# ArtFire_1.net
KiCad netlist of a schematic drawn in Altium Designer
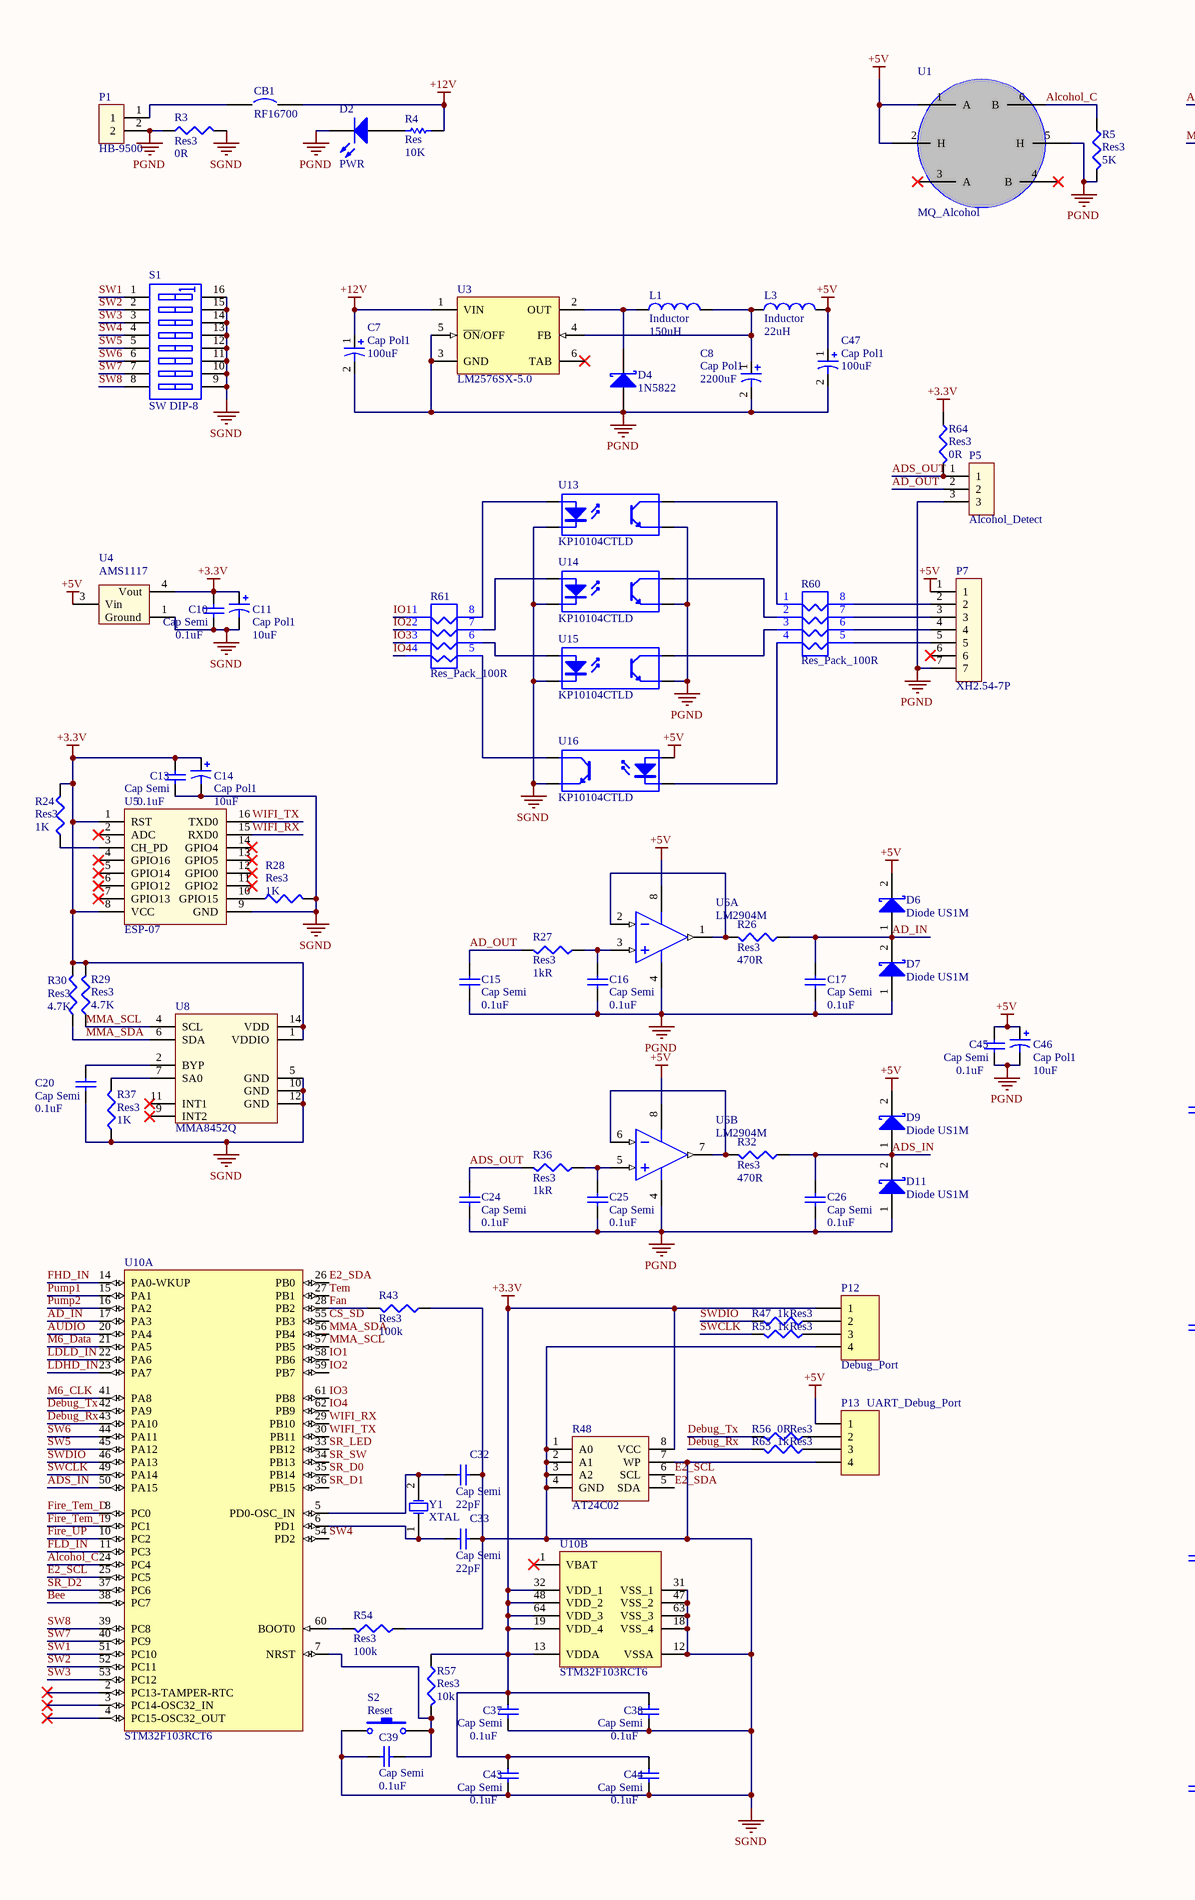
[diagram p0: ArtFire (1).SchDoc, left]
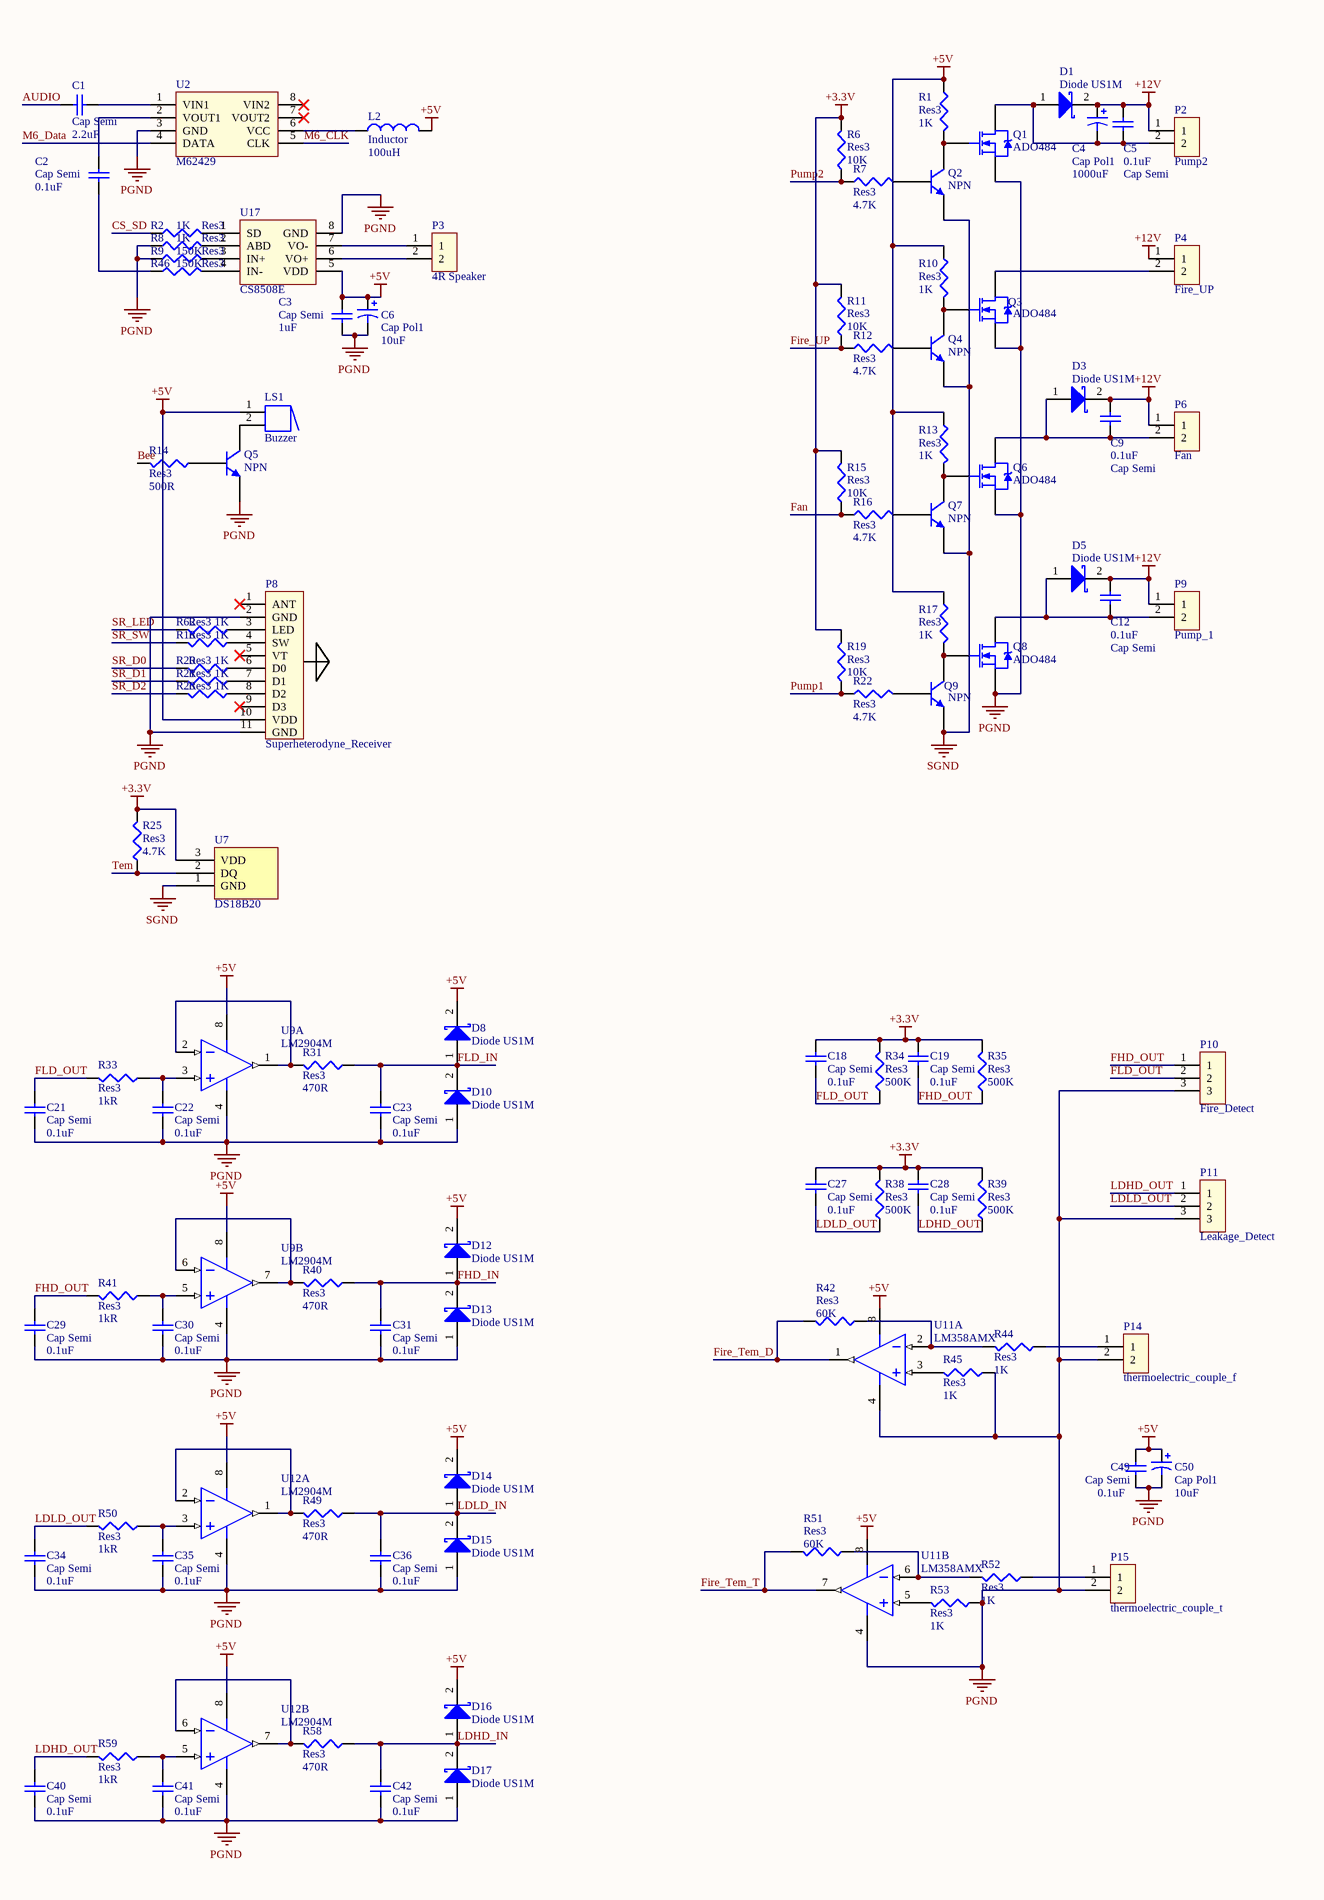
[diagram p1: ArtFire (1).SchDoc, right]

(export (version "E")
  (design (tool "Eeschema 10.0.6"))
  (components
    (comp (ref "C1")
      (value "Cap Semi")
      (footprint "6-0805_N")
      (description "Capacitor (Semiconductor SIM Model)")
      (fields (field (name "ALTIUM_VALUE") "2.2uF") (field (name "PUBLISHER") "Altium Limited"))
      (libsource (lib "Miscellaneous Devices") (part "Cap Semi"))
    )
    (comp (ref "C2")
      (value "Cap Semi")
      (footprint "6-0805_N")
      (description "Capacitor (Semiconductor SIM Model)")
      (fields (field (name "ALTIUM_VALUE") "0.1uF") (field (name "PUBLISHER") "Altium Limited"))
      (libsource (lib "Miscellaneous Devices") (part "Cap Semi"))
    )
    (comp (ref "C3")
      (value "Cap Semi")
      (footprint "6-0805_N")
      (description "Capacitor (Semiconductor SIM Model)")
      (fields (field (name "ALTIUM_VALUE") "1uF") (field (name "PUBLISHER") "Altium Limited"))
      (libsource (lib "Miscellaneous Devices") (part "Cap Semi"))
    )
    (comp (ref "C4")
      (value "Cap Pol1")
      (footprint "CAP_10*10MM")
      (description "Polarized Capacitor (Radial)")
      (fields (field (name "ALTIUM_VALUE") "1000uF") (field (name "PUBLISHER") "Altium Limited"))
      (libsource (lib "Miscellaneous Devices") (part "Cap Pol1"))
    )
    (comp (ref "C5")
      (value "Cap Semi")
      (footprint "6-0805_N")
      (description "Capacitor (Semiconductor SIM Model)")
      (fields (field (name "ALTIUM_VALUE") "0.1uF") (field (name "PUBLISHER") "Altium Limited"))
      (libsource (lib "Miscellaneous Devices") (part "Cap Semi"))
    )
    (comp (ref "C6")
      (value "Cap Pol1")
      (footprint "Cap_5*4mm")
      (description "Polarized Capacitor (Radial)")
      (fields (field (name "ALTIUM_VALUE") "10uF") (field (name "PUBLISHER") "Altium Limited"))
      (libsource (lib "Miscellaneous Devices") (part "Cap Pol1"))
    )
    (comp (ref "C7")
      (value "Cap Pol1")
      (footprint "CAP_6.3*5.4MM")
      (description "Polarized Capacitor (Radial)")
      (fields (field (name "ALTIUM_VALUE") "100uF") (field (name "PUBLISHER") "Altium Limited"))
      (libsource (lib "") (part "Cap Pol1_1"))
    )
    (comp (ref "C8")
      (value "Cap Pol1")
      (footprint "CAP10_17")
      (description "Polarized Capacitor (Radial)")
      (fields (field (name "ALTIUM_VALUE") "2200uF") (field (name "PUBLISHER") "Altium Limited"))
      (libsource (lib "") (part "Cap Pol1_1"))
    )
    (comp (ref "C9")
      (value "Cap Semi")
      (footprint "6-0805_N")
      (description "Capacitor (Semiconductor SIM Model)")
      (fields (field (name "ALTIUM_VALUE") "0.1uF") (field (name "PUBLISHER") "Altium Limited"))
      (libsource (lib "Miscellaneous Devices") (part "Cap Semi"))
    )
    (comp (ref "C10")
      (value "Cap Semi")
      (footprint "6-0805_N")
      (description "Capacitor (Semiconductor SIM Model)")
      (fields (field (name "ALTIUM_VALUE") "0.1uF") (field (name "PUBLISHER") "Altium Limited"))
      (libsource (lib "Miscellaneous Devices") (part "Cap Semi"))
    )
    (comp (ref "C11")
      (value "Cap Pol1")
      (footprint "Cap_5*4mm")
      (description "Polarized Capacitor (Radial)")
      (fields (field (name "ALTIUM_VALUE") "10uF") (field (name "PUBLISHER") "Altium Limited"))
      (libsource (lib "Miscellaneous Devices") (part "Cap Pol1"))
    )
    (comp (ref "C12")
      (value "Cap Semi")
      (footprint "6-0805_N")
      (description "Capacitor (Semiconductor SIM Model)")
      (fields (field (name "ALTIUM_VALUE") "0.1uF") (field (name "PUBLISHER") "Altium Limited"))
      (libsource (lib "Miscellaneous Devices") (part "Cap Semi"))
    )
    (comp (ref "C13")
      (value "Cap Semi")
      (footprint "6-0805_N")
      (description "Capacitor (Semiconductor SIM Model)")
      (fields (field (name "ALTIUM_VALUE") "0.1uF") (field (name "PUBLISHER") "Altium Limited"))
      (libsource (lib "Miscellaneous Devices") (part "Cap Semi"))
    )
    (comp (ref "C14")
      (value "Cap Pol1")
      (footprint "Cap_5*4mm")
      (description "Polarized Capacitor (Radial)")
      (fields (field (name "ALTIUM_VALUE") "10uF") (field (name "PUBLISHER") "Altium Limited"))
      (libsource (lib "Miscellaneous Devices") (part "Cap Pol1"))
    )
    (comp (ref "C15")
      (value "Cap Semi")
      (footprint "6-0805_N")
      (description "Capacitor (Semiconductor SIM Model)")
      (fields (field (name "ALTIUM_VALUE") "0.1uF") (field (name "PUBLISHER") "Altium Limited"))
      (libsource (lib "Miscellaneous Devices") (part "Cap Semi"))
    )
    (comp (ref "C16")
      (value "Cap Semi")
      (footprint "6-0805_N")
      (description "Capacitor (Semiconductor SIM Model)")
      (fields (field (name "ALTIUM_VALUE") "0.1uF") (field (name "PUBLISHER") "Altium Limited"))
      (libsource (lib "Miscellaneous Devices") (part "Cap Semi"))
    )
    (comp (ref "C17")
      (value "Cap Semi")
      (footprint "6-0805_N")
      (description "Capacitor (Semiconductor SIM Model)")
      (fields (field (name "ALTIUM_VALUE") "0.1uF") (field (name "PUBLISHER") "Altium Limited"))
      (libsource (lib "Miscellaneous Devices") (part "Cap Semi"))
    )
    (comp (ref "C18")
      (value "Cap Semi")
      (footprint "6-0805_N")
      (description "Capacitor (Semiconductor SIM Model)")
      (fields (field (name "ALTIUM_VALUE") "0.1uF") (field (name "PUBLISHER") "Altium Limited"))
      (libsource (lib "Miscellaneous Devices") (part "Cap Semi"))
    )
    (comp (ref "C19")
      (value "Cap Semi")
      (footprint "6-0805_N")
      (description "Capacitor (Semiconductor SIM Model)")
      (fields (field (name "ALTIUM_VALUE") "0.1uF") (field (name "PUBLISHER") "Altium Limited"))
      (libsource (lib "Miscellaneous Devices") (part "Cap Semi"))
    )
    (comp (ref "C20")
      (value "Cap Semi")
      (footprint "6-0805_N")
      (description "Capacitor (Semiconductor SIM Model)")
      (fields (field (name "ALTIUM_VALUE") "0.1uF") (field (name "PUBLISHER") "Altium Limited"))
      (libsource (lib "Miscellaneous Devices") (part "Cap Semi"))
    )
    (comp (ref "C21")
      (value "Cap Semi")
      (footprint "6-0805_N")
      (description "Capacitor (Semiconductor SIM Model)")
      (fields (field (name "ALTIUM_VALUE") "0.1uF") (field (name "PUBLISHER") "Altium Limited"))
      (libsource (lib "Miscellaneous Devices") (part "Cap Semi"))
    )
    (comp (ref "C22")
      (value "Cap Semi")
      (footprint "6-0805_N")
      (description "Capacitor (Semiconductor SIM Model)")
      (fields (field (name "ALTIUM_VALUE") "0.1uF") (field (name "PUBLISHER") "Altium Limited"))
      (libsource (lib "Miscellaneous Devices") (part "Cap Semi"))
    )
    (comp (ref "C23")
      (value "Cap Semi")
      (footprint "6-0805_N")
      (description "Capacitor (Semiconductor SIM Model)")
      (fields (field (name "ALTIUM_VALUE") "0.1uF") (field (name "PUBLISHER") "Altium Limited"))
      (libsource (lib "Miscellaneous Devices") (part "Cap Semi"))
    )
    (comp (ref "C24")
      (value "Cap Semi")
      (footprint "6-0805_N")
      (description "Capacitor (Semiconductor SIM Model)")
      (fields (field (name "ALTIUM_VALUE") "0.1uF") (field (name "PUBLISHER") "Altium Limited"))
      (libsource (lib "Miscellaneous Devices") (part "Cap Semi"))
    )
    (comp (ref "C25")
      (value "Cap Semi")
      (footprint "6-0805_N")
      (description "Capacitor (Semiconductor SIM Model)")
      (fields (field (name "ALTIUM_VALUE") "0.1uF") (field (name "PUBLISHER") "Altium Limited"))
      (libsource (lib "Miscellaneous Devices") (part "Cap Semi"))
    )
    (comp (ref "C26")
      (value "Cap Semi")
      (footprint "6-0805_N")
      (description "Capacitor (Semiconductor SIM Model)")
      (fields (field (name "ALTIUM_VALUE") "0.1uF") (field (name "PUBLISHER") "Altium Limited"))
      (libsource (lib "Miscellaneous Devices") (part "Cap Semi"))
    )
    (comp (ref "C27")
      (value "Cap Semi")
      (footprint "6-0805_N")
      (description "Capacitor (Semiconductor SIM Model)")
      (fields (field (name "ALTIUM_VALUE") "0.1uF") (field (name "PUBLISHER") "Altium Limited"))
      (libsource (lib "Miscellaneous Devices") (part "Cap Semi"))
    )
    (comp (ref "C28")
      (value "Cap Semi")
      (footprint "6-0805_N")
      (description "Capacitor (Semiconductor SIM Model)")
      (fields (field (name "ALTIUM_VALUE") "0.1uF") (field (name "PUBLISHER") "Altium Limited"))
      (libsource (lib "Miscellaneous Devices") (part "Cap Semi"))
    )
    (comp (ref "C29")
      (value "Cap Semi")
      (footprint "6-0805_N")
      (description "Capacitor (Semiconductor SIM Model)")
      (fields (field (name "ALTIUM_VALUE") "0.1uF") (field (name "PUBLISHER") "Altium Limited"))
      (libsource (lib "Miscellaneous Devices") (part "Cap Semi"))
    )
    (comp (ref "C30")
      (value "Cap Semi")
      (footprint "6-0805_N")
      (description "Capacitor (Semiconductor SIM Model)")
      (fields (field (name "ALTIUM_VALUE") "0.1uF") (field (name "PUBLISHER") "Altium Limited"))
      (libsource (lib "Miscellaneous Devices") (part "Cap Semi"))
    )
    (comp (ref "C31")
      (value "Cap Semi")
      (footprint "6-0805_N")
      (description "Capacitor (Semiconductor SIM Model)")
      (fields (field (name "ALTIUM_VALUE") "0.1uF") (field (name "PUBLISHER") "Altium Limited"))
      (libsource (lib "Miscellaneous Devices") (part "Cap Semi"))
    )
    (comp (ref "C32")
      (value "Cap Semi")
      (footprint "6-0805_N")
      (description "Capacitor (Semiconductor SIM Model)")
      (fields (field (name "ALTIUM_VALUE") "22pF") (field (name "PUBLISHER") "Altium Limited"))
      (libsource (lib "Miscellaneous Devices") (part "Cap Semi"))
    )
    (comp (ref "C33")
      (value "Cap Semi")
      (footprint "6-0805_N")
      (description "Capacitor (Semiconductor SIM Model)")
      (fields (field (name "ALTIUM_VALUE") "22pF") (field (name "PUBLISHER") "Altium Limited"))
      (libsource (lib "Miscellaneous Devices") (part "Cap Semi"))
    )
    (comp (ref "C34")
      (value "Cap Semi")
      (footprint "6-0805_N")
      (description "Capacitor (Semiconductor SIM Model)")
      (fields (field (name "ALTIUM_VALUE") "0.1uF") (field (name "PUBLISHER") "Altium Limited"))
      (libsource (lib "Miscellaneous Devices") (part "Cap Semi"))
    )
    (comp (ref "C35")
      (value "Cap Semi")
      (footprint "6-0805_N")
      (description "Capacitor (Semiconductor SIM Model)")
      (fields (field (name "ALTIUM_VALUE") "0.1uF") (field (name "PUBLISHER") "Altium Limited"))
      (libsource (lib "Miscellaneous Devices") (part "Cap Semi"))
    )
    (comp (ref "C36")
      (value "Cap Semi")
      (footprint "6-0805_N")
      (description "Capacitor (Semiconductor SIM Model)")
      (fields (field (name "ALTIUM_VALUE") "0.1uF") (field (name "PUBLISHER") "Altium Limited"))
      (libsource (lib "Miscellaneous Devices") (part "Cap Semi"))
    )
    (comp (ref "C37")
      (value "Cap Semi")
      (footprint "6-0805_N")
      (description "Capacitor (Semiconductor SIM Model)")
      (fields (field (name "ALTIUM_VALUE") "0.1uF") (field (name "PUBLISHER") "Altium Limited"))
      (libsource (lib "Miscellaneous Devices") (part "Cap Semi"))
    )
    (comp (ref "C38")
      (value "Cap Semi")
      (footprint "6-0805_N")
      (description "Capacitor (Semiconductor SIM Model)")
      (fields (field (name "ALTIUM_VALUE") "0.1uF") (field (name "PUBLISHER") "Altium Limited"))
      (libsource (lib "Miscellaneous Devices") (part "Cap Semi"))
    )
    (comp (ref "C39")
      (value "Cap Semi")
      (footprint "6-0805_N")
      (description "Capacitor (Semiconductor SIM Model)")
      (fields (field (name "ALTIUM_VALUE") "0.1uF") (field (name "PUBLISHER") "Altium Limited"))
      (libsource (lib "Miscellaneous Devices") (part "Cap Semi"))
    )
    (comp (ref "C40")
      (value "Cap Semi")
      (footprint "6-0805_N")
      (description "Capacitor (Semiconductor SIM Model)")
      (fields (field (name "ALTIUM_VALUE") "0.1uF") (field (name "PUBLISHER") "Altium Limited"))
      (libsource (lib "Miscellaneous Devices") (part "Cap Semi"))
    )
    (comp (ref "C41")
      (value "Cap Semi")
      (footprint "6-0805_N")
      (description "Capacitor (Semiconductor SIM Model)")
      (fields (field (name "ALTIUM_VALUE") "0.1uF") (field (name "PUBLISHER") "Altium Limited"))
      (libsource (lib "Miscellaneous Devices") (part "Cap Semi"))
    )
    (comp (ref "C42")
      (value "Cap Semi")
      (footprint "6-0805_N")
      (description "Capacitor (Semiconductor SIM Model)")
      (fields (field (name "ALTIUM_VALUE") "0.1uF") (field (name "PUBLISHER") "Altium Limited"))
      (libsource (lib "Miscellaneous Devices") (part "Cap Semi"))
    )
    (comp (ref "C43")
      (value "Cap Semi")
      (footprint "6-0805_N")
      (description "Capacitor (Semiconductor SIM Model)")
      (fields (field (name "ALTIUM_VALUE") "0.1uF") (field (name "PUBLISHER") "Altium Limited"))
      (libsource (lib "Miscellaneous Devices") (part "Cap Semi"))
    )
    (comp (ref "C44")
      (value "Cap Semi")
      (footprint "6-0805_N")
      (description "Capacitor (Semiconductor SIM Model)")
      (fields (field (name "ALTIUM_VALUE") "0.1uF") (field (name "PUBLISHER") "Altium Limited"))
      (libsource (lib "Miscellaneous Devices") (part "Cap Semi"))
    )
    (comp (ref "C45")
      (value "Cap Semi")
      (footprint "6-0805_N")
      (description "Capacitor (Semiconductor SIM Model)")
      (fields (field (name "ALTIUM_VALUE") "0.1uF") (field (name "PUBLISHER") "Altium Limited"))
      (libsource (lib "Miscellaneous Devices") (part "Cap Semi"))
    )
    (comp (ref "C46")
      (value "Cap Pol1")
      (footprint "Cap_5*4mm")
      (description "Polarized Capacitor (Radial)")
      (fields (field (name "ALTIUM_VALUE") "10uF") (field (name "PUBLISHER") "Altium Limited"))
      (libsource (lib "Miscellaneous Devices") (part "Cap Pol1"))
    )
    (comp (ref "C47")
      (value "Cap Pol1")
      (footprint "CAP_6.3*5.4MM")
      (description "Polarized Capacitor (Radial)")
      (fields (field (name "ALTIUM_VALUE") "100uF") (field (name "PUBLISHER") "Altium Limited"))
      (libsource (lib "") (part "Cap Pol1_1"))
    )
    (comp (ref "C49")
      (value "Cap Semi")
      (footprint "6-0805_N")
      (description "Capacitor (Semiconductor SIM Model)")
      (fields (field (name "ALTIUM_VALUE") "0.1uF") (field (name "PUBLISHER") "Altium Limited"))
      (libsource (lib "Miscellaneous Devices") (part "Cap Semi"))
    )
    (comp (ref "C50")
      (value "Cap Pol1")
      (footprint "Cap_5*4mm")
      (description "Polarized Capacitor (Radial)")
      (fields (field (name "ALTIUM_VALUE") "10uF") (field (name "PUBLISHER") "Altium Limited"))
      (libsource (lib "Miscellaneous Devices") (part "Cap Pol1"))
    )
    (comp (ref "CB1")
      (value "RF16700")
      (footprint "SPST-2")
      (description "Circuit Breaker")
      (fields (field (name "PUBLISHER") "Altium Limited"))
      (libsource (lib "Miscellaneous Devices") (part "Circuit Breaker"))
    )
    (comp (ref "D1")
      (value "Diode US1M")
      (footprint "US1M")
      (description "Silicon RF Schottky Diode for Mixer Applications in the VHF/UHF Range")
      (fields (field (name "PUBLISHER") "Altium Limited"))
      (libsource (lib "Miscellaneous Devices") (part "Diode BAT17"))
    )
    (comp (ref "D2")
      (value "PWR")
      (footprint "6-0805_N")
      (description "Typical INFRARED GaAs LED")
      (fields (field (name "PUBLISHER") "Altium Limited"))
      (libsource (lib "Miscellaneous Devices") (part "LED0"))
    )
    (comp (ref "D3")
      (value "Diode US1M")
      (footprint "US1M")
      (description "Silicon RF Schottky Diode for Mixer Applications in the VHF/UHF Range")
      (fields (field (name "PUBLISHER") "Altium Limited"))
      (libsource (lib "Miscellaneous Devices") (part "Diode BAT17"))
    )
    (comp (ref "D4")
      (value "1N5822")
      (footprint "US1M")
      (description "Silicon RF Schottky Diode for Mixer Applications in the VHF/UHF Range")
      (fields (field (name "PUBLISHER") "Altium Limited"))
      (libsource (lib "") (part "Diode BAT17_1"))
    )
    (comp (ref "D5")
      (value "Diode US1M")
      (footprint "US1M")
      (description "Silicon RF Schottky Diode for Mixer Applications in the VHF/UHF Range")
      (fields (field (name "PUBLISHER") "Altium Limited"))
      (libsource (lib "Miscellaneous Devices") (part "Diode BAT17"))
    )
    (comp (ref "D6")
      (value "Diode US1M")
      (footprint "US1M")
      (description "Silicon RF Schottky Diode for Mixer Applications in the VHF/UHF Range")
      (fields (field (name "PUBLISHER") "Altium Limited"))
      (libsource (lib "Miscellaneous Devices") (part "Diode BAT17"))
    )
    (comp (ref "D7")
      (value "Diode US1M")
      (footprint "US1M")
      (description "Silicon RF Schottky Diode for Mixer Applications in the VHF/UHF Range")
      (fields (field (name "PUBLISHER") "Altium Limited"))
      (libsource (lib "Miscellaneous Devices") (part "Diode BAT17"))
    )
    (comp (ref "D8")
      (value "Diode US1M")
      (footprint "US1M")
      (description "Silicon RF Schottky Diode for Mixer Applications in the VHF/UHF Range")
      (fields (field (name "PUBLISHER") "Altium Limited"))
      (libsource (lib "Miscellaneous Devices") (part "Diode BAT17"))
    )
    (comp (ref "D9")
      (value "Diode US1M")
      (footprint "US1M")
      (description "Silicon RF Schottky Diode for Mixer Applications in the VHF/UHF Range")
      (fields (field (name "PUBLISHER") "Altium Limited"))
      (libsource (lib "Miscellaneous Devices") (part "Diode BAT17"))
    )
    (comp (ref "D10")
      (value "Diode US1M")
      (footprint "US1M")
      (description "Silicon RF Schottky Diode for Mixer Applications in the VHF/UHF Range")
      (fields (field (name "PUBLISHER") "Altium Limited"))
      (libsource (lib "Miscellaneous Devices") (part "Diode BAT17"))
    )
    (comp (ref "D11")
      (value "Diode US1M")
      (footprint "US1M")
      (description "Silicon RF Schottky Diode for Mixer Applications in the VHF/UHF Range")
      (fields (field (name "PUBLISHER") "Altium Limited"))
      (libsource (lib "Miscellaneous Devices") (part "Diode BAT17"))
    )
    (comp (ref "D12")
      (value "Diode US1M")
      (footprint "US1M")
      (description "Silicon RF Schottky Diode for Mixer Applications in the VHF/UHF Range")
      (fields (field (name "PUBLISHER") "Altium Limited"))
      (libsource (lib "Miscellaneous Devices") (part "Diode BAT17"))
    )
    (comp (ref "D13")
      (value "Diode US1M")
      (footprint "US1M")
      (description "Silicon RF Schottky Diode for Mixer Applications in the VHF/UHF Range")
      (fields (field (name "PUBLISHER") "Altium Limited"))
      (libsource (lib "Miscellaneous Devices") (part "Diode BAT17"))
    )
    (comp (ref "D14")
      (value "Diode US1M")
      (footprint "US1M")
      (description "Silicon RF Schottky Diode for Mixer Applications in the VHF/UHF Range")
      (fields (field (name "PUBLISHER") "Altium Limited"))
      (libsource (lib "Miscellaneous Devices") (part "Diode BAT17"))
    )
    (comp (ref "D15")
      (value "Diode US1M")
      (footprint "US1M")
      (description "Silicon RF Schottky Diode for Mixer Applications in the VHF/UHF Range")
      (fields (field (name "PUBLISHER") "Altium Limited"))
      (libsource (lib "Miscellaneous Devices") (part "Diode BAT17"))
    )
    (comp (ref "D16")
      (value "Diode US1M")
      (footprint "US1M")
      (description "Silicon RF Schottky Diode for Mixer Applications in the VHF/UHF Range")
      (fields (field (name "PUBLISHER") "Altium Limited"))
      (libsource (lib "Miscellaneous Devices") (part "Diode BAT17"))
    )
    (comp (ref "D17")
      (value "Diode US1M")
      (footprint "US1M")
      (description "Silicon RF Schottky Diode for Mixer Applications in the VHF/UHF Range")
      (fields (field (name "PUBLISHER") "Altium Limited"))
      (libsource (lib "Miscellaneous Devices") (part "Diode BAT17"))
    )
    (comp (ref "L1")
      (value "Inductor")
      (footprint "CDRH127")
      (fields (field (name "ALTIUM_VALUE") "150uH") (field (name "PUBLISHER") "Altium Limited"))
      (libsource (lib "Miscellaneous Devices") (part "Inductor"))
    )
    (comp (ref "L2")
      (value "Inductor")
      (footprint "6-0805_L")
      (fields (field (name "ALTIUM_VALUE") "100uH") (field (name "PUBLISHER") "Altium Limited"))
      (libsource (lib "Miscellaneous Devices") (part "Inductor"))
    )
    (comp (ref "L3")
      (value "Inductor")
      (footprint "IND_0630")
      (fields (field (name "ALTIUM_VALUE") "22uH") (field (name "PUBLISHER") "Altium Limited"))
      (libsource (lib "Miscellaneous Devices") (part "Inductor"))
    )
    (comp (ref "LS1")
      (value "Buzzer")
      (footprint "BUZZER")
      (description "Magnetic Transducer Buzzer")
      (fields (field (name "PUBLISHER") "Altium Limited"))
      (libsource (lib "Miscellaneous Devices") (part "Buzzer"))
    )
    (comp (ref "P1")
      (value "HB-9500")
      (footprint "HB-9500")
      (description "High current connector")
      (libsource (lib "Simon'Library") (part "HB-9500"))
    )
    (comp (ref "P2") (value "Pump2") (footprint "CH3.96_2P") (libsource (lib "CH3.96") (part "CH3.96_2P")))
    (comp (ref "P3")
      (value "4R Speaker")
      (footprint "XH2.54-2P")
      (libsource (lib "XH2.54") (part "XH2.54-2P"))
    )
    (comp (ref "P4") (value "Fire_UP") (footprint "KF7.62-2P") (libsource (lib "KF3.96") (part "KF3.96")))
    (comp (ref "P5")
      (value "Alcohol_Detect")
      (footprint "XH2.54-3P")
      (libsource (lib "XH2.54") (part "XH2.54-3P"))
    )
    (comp (ref "P6") (value "Fan") (footprint "XH2.54-2P") (libsource (lib "XH2.54") (part "XH2.54-2P")))
    (comp (ref "P7")
      (value "XH2.54-7P")
      (footprint "XH2.54-7P")
      (libsource (lib "XH2.54") (part "XH2.54-7P"))
    )
    (comp (ref "P8")
      (value "Superheterodyne_Receiver")
      (footprint "Sperheterodyne_Receiver")
      (libsource (lib "Simon'Library") (part "Superheterodyne_Receiver"))
    )
    (comp (ref "P9") (value "Pump_1") (footprint "CH3.96_2P") (libsource (lib "CH3.96") (part "CH3.96_2P")))
    (comp (ref "P10")
      (value "Fire_Detect")
      (footprint "CH3.96_3P")
      (libsource (lib "CH3.96") (part "CH3.96_3P"))
    )
    (comp (ref "P11")
      (value "Leakage_Detect")
      (footprint "XH2.54-3P")
      (libsource (lib "XH2.54") (part "XH2.54-3P"))
    )
    (comp (ref "P12")
      (value "Debug_Port")
      (footprint "HDR1X4")
      (description "Header, 4-Pin")
      (fields (field (name "PUBLISHER") "Altium Limited"))
      (libsource (lib "Miscellaneous Connectors") (part "Header 4"))
    )
    (comp (ref "P13")
      (value "UART_Debug_Port")
      (footprint "HDR1X4")
      (description "Header, 4-Pin")
      (fields (field (name "PUBLISHER") "Altium Limited"))
      (libsource (lib "Miscellaneous Connectors") (part "Header 4"))
    )
    (comp (ref "P14")
      (value "thermoelectric_couple_f")
      (footprint "KF7.62-2P")
      (libsource (lib "KF3.96") (part "KF3.96"))
    )
    (comp (ref "P15")
      (value "thermoelectric_couple_t")
      (footprint "KF7.62-2P")
      (libsource (lib "KF3.96") (part "KF3.96"))
    )
    (comp (ref "Q1")
      (value "ADO484")
      (footprint "DPAK_AOD484")
      (description "N-Channel Power MOSFET")
      (fields (field (name "PUBLISHER") "Altium Limited"))
      (libsource (lib "Miscellaneous Devices") (part "NMOS-2"))
    )
    (comp (ref "Q2")
      (value "NPN")
      (footprint "SOT-23_N")
      (description "NPN Bipolar Transistor")
      (fields (field (name "PUBLISHER") "Altium Limited"))
      (libsource (lib "Miscellaneous Devices") (part "NPN"))
    )
    (comp (ref "Q3")
      (value "ADO484")
      (footprint "DPAK_AOD484")
      (description "N-Channel Power MOSFET")
      (fields (field (name "PUBLISHER") "Altium Limited"))
      (libsource (lib "Miscellaneous Devices") (part "NMOS-2"))
    )
    (comp (ref "Q4")
      (value "NPN")
      (footprint "SOT-23_N")
      (description "NPN Bipolar Transistor")
      (fields (field (name "PUBLISHER") "Altium Limited"))
      (libsource (lib "Miscellaneous Devices") (part "NPN"))
    )
    (comp (ref "Q5")
      (value "NPN")
      (footprint "SOT-23_N")
      (description "NPN Bipolar Transistor")
      (fields (field (name "PUBLISHER") "Altium Limited"))
      (libsource (lib "Miscellaneous Devices") (part "NPN"))
    )
    (comp (ref "Q6")
      (value "ADO484")
      (footprint "DPAK_AOD484")
      (description "N-Channel Power MOSFET")
      (fields (field (name "PUBLISHER") "Altium Limited"))
      (libsource (lib "Miscellaneous Devices") (part "NMOS-2"))
    )
    (comp (ref "Q7")
      (value "NPN")
      (footprint "SOT-23_N")
      (description "NPN Bipolar Transistor")
      (fields (field (name "PUBLISHER") "Altium Limited"))
      (libsource (lib "Miscellaneous Devices") (part "NPN"))
    )
    (comp (ref "Q8")
      (value "ADO484")
      (footprint "DPAK_AOD484")
      (description "N-Channel Power MOSFET")
      (fields (field (name "PUBLISHER") "Altium Limited"))
      (libsource (lib "Miscellaneous Devices") (part "NMOS-2"))
    )
    (comp (ref "Q9")
      (value "NPN")
      (footprint "SOT-23_N")
      (description "NPN Bipolar Transistor")
      (fields (field (name "PUBLISHER") "Altium Limited"))
      (libsource (lib "Miscellaneous Devices") (part "NPN"))
    )
    (comp (ref "R1")
      (value "Res3")
      (footprint "6-0805_N")
      (description "Resistor")
      (fields (field (name "ALTIUM_VALUE") "1K") (field (name "PUBLISHER") "Altium Limited"))
      (libsource (lib "Miscellaneous Devices") (part "Res3"))
    )
    (comp (ref "R2")
      (value "Res3")
      (footprint "6-0805_N")
      (description "Resistor")
      (fields (field (name "ALTIUM_VALUE") "1K") (field (name "PUBLISHER") "Altium Limited"))
      (libsource (lib "Miscellaneous Devices") (part "Res3"))
    )
    (comp (ref "R3")
      (value "Res3")
      (footprint "6-0805_N")
      (description "Resistor")
      (fields (field (name "ALTIUM_VALUE") "0R") (field (name "PUBLISHER") "Altium Limited"))
      (libsource (lib "Miscellaneous Devices") (part "Res3"))
    )
    (comp (ref "R4")
      (value "Res")
      (footprint "6-0805_N")
      (description "Resistor")
      (fields (field (name "ALTIUM_VALUE") "10K") (field (name "PUBLISHER") "Altium Limited"))
      (libsource (lib "Miscellaneous Devices") (part "Res1"))
    )
    (comp (ref "R5")
      (value "Res3")
      (footprint "6-0805_N")
      (description "Resistor")
      (fields (field (name "ALTIUM_VALUE") "5K") (field (name "PUBLISHER") "Altium Limited"))
      (libsource (lib "Miscellaneous Devices") (part "Res3"))
    )
    (comp (ref "R6")
      (value "Res3")
      (footprint "6-0805_N")
      (description "Resistor")
      (fields (field (name "ALTIUM_VALUE") "10K") (field (name "PUBLISHER") "Altium Limited"))
      (libsource (lib "Miscellaneous Devices") (part "Res3"))
    )
    (comp (ref "R7")
      (value "Res3")
      (footprint "6-0805_N")
      (description "Resistor")
      (fields (field (name "ALTIUM_VALUE") "4.7K") (field (name "PUBLISHER") "Altium Limited"))
      (libsource (lib "Miscellaneous Devices") (part "Res3"))
    )
    (comp (ref "R8")
      (value "Res3")
      (footprint "6-0805_N")
      (description "Resistor")
      (fields (field (name "ALTIUM_VALUE") "1K") (field (name "PUBLISHER") "Altium Limited"))
      (libsource (lib "Miscellaneous Devices") (part "Res3"))
    )
    (comp (ref "R9")
      (value "Res3")
      (footprint "6-0805_N")
      (description "Resistor")
      (fields (field (name "ALTIUM_VALUE") "150K") (field (name "PUBLISHER") "Altium Limited"))
      (libsource (lib "Miscellaneous Devices") (part "Res3"))
    )
    (comp (ref "R10")
      (value "Res3")
      (footprint "6-0805_N")
      (description "Resistor")
      (fields (field (name "ALTIUM_VALUE") "1K") (field (name "PUBLISHER") "Altium Limited"))
      (libsource (lib "Miscellaneous Devices") (part "Res3"))
    )
    (comp (ref "R11")
      (value "Res3")
      (footprint "6-0805_N")
      (description "Resistor")
      (fields (field (name "ALTIUM_VALUE") "10K") (field (name "PUBLISHER") "Altium Limited"))
      (libsource (lib "Miscellaneous Devices") (part "Res3"))
    )
    (comp (ref "R12")
      (value "Res3")
      (footprint "6-0805_N")
      (description "Resistor")
      (fields (field (name "ALTIUM_VALUE") "4.7K") (field (name "PUBLISHER") "Altium Limited"))
      (libsource (lib "Miscellaneous Devices") (part "Res3"))
    )
    (comp (ref "R13")
      (value "Res3")
      (footprint "6-0805_N")
      (description "Resistor")
      (fields (field (name "ALTIUM_VALUE") "1K") (field (name "PUBLISHER") "Altium Limited"))
      (libsource (lib "Miscellaneous Devices") (part "Res3"))
    )
    (comp (ref "R14")
      (value "Res3")
      (footprint "6-0805_N")
      (description "Resistor")
      (fields (field (name "ALTIUM_VALUE") "500R") (field (name "PUBLISHER") "Altium Limited"))
      (libsource (lib "Miscellaneous Devices") (part "Res3"))
    )
    (comp (ref "R15")
      (value "Res3")
      (footprint "6-0805_N")
      (description "Resistor")
      (fields (field (name "ALTIUM_VALUE") "10K") (field (name "PUBLISHER") "Altium Limited"))
      (libsource (lib "Miscellaneous Devices") (part "Res3"))
    )
    (comp (ref "R16")
      (value "Res3")
      (footprint "6-0805_N")
      (description "Resistor")
      (fields (field (name "ALTIUM_VALUE") "4.7K") (field (name "PUBLISHER") "Altium Limited"))
      (libsource (lib "Miscellaneous Devices") (part "Res3"))
    )
    (comp (ref "R17")
      (value "Res3")
      (footprint "6-0805_N")
      (description "Resistor")
      (fields (field (name "ALTIUM_VALUE") "1K") (field (name "PUBLISHER") "Altium Limited"))
      (libsource (lib "Miscellaneous Devices") (part "Res3"))
    )
    (comp (ref "R18")
      (value "Res3")
      (footprint "6-0805_N")
      (description "Resistor")
      (fields (field (name "ALTIUM_VALUE") "1K") (field (name "PUBLISHER") "Altium Limited"))
      (libsource (lib "Miscellaneous Devices") (part "Res3"))
    )
    (comp (ref "R19")
      (value "Res3")
      (footprint "6-0805_N")
      (description "Resistor")
      (fields (field (name "ALTIUM_VALUE") "10K") (field (name "PUBLISHER") "Altium Limited"))
      (libsource (lib "Miscellaneous Devices") (part "Res3"))
    )
    (comp (ref "R20")
      (value "Res3")
      (footprint "6-0805_N")
      (description "Resistor")
      (fields (field (name "ALTIUM_VALUE") "1K") (field (name "PUBLISHER") "Altium Limited"))
      (libsource (lib "Miscellaneous Devices") (part "Res3"))
    )
    (comp (ref "R21")
      (value "Res3")
      (footprint "6-0805_N")
      (description "Resistor")
      (fields (field (name "ALTIUM_VALUE") "1K") (field (name "PUBLISHER") "Altium Limited"))
      (libsource (lib "Miscellaneous Devices") (part "Res3"))
    )
    (comp (ref "R22")
      (value "Res3")
      (footprint "6-0805_N")
      (description "Resistor")
      (fields (field (name "ALTIUM_VALUE") "4.7K") (field (name "PUBLISHER") "Altium Limited"))
      (libsource (lib "Miscellaneous Devices") (part "Res3"))
    )
    (comp (ref "R23")
      (value "Res3")
      (footprint "6-0805_N")
      (description "Resistor")
      (fields (field (name "ALTIUM_VALUE") "1K") (field (name "PUBLISHER") "Altium Limited"))
      (libsource (lib "Miscellaneous Devices") (part "Res3"))
    )
    (comp (ref "R24")
      (value "Res3")
      (footprint "6-0805_N")
      (description "Resistor")
      (fields (field (name "ALTIUM_VALUE") "1K") (field (name "PUBLISHER") "Altium Limited"))
      (libsource (lib "Miscellaneous Devices") (part "Res3"))
    )
    (comp (ref "R25")
      (value "Res3")
      (footprint "6-0805_N")
      (description "Resistor")
      (fields (field (name "ALTIUM_VALUE") "4.7K") (field (name "PUBLISHER") "Altium Limited"))
      (libsource (lib "Miscellaneous Devices") (part "Res3"))
    )
    (comp (ref "R26")
      (value "Res3")
      (footprint "6-0805_N")
      (description "Resistor")
      (fields (field (name "ALTIUM_VALUE") "470R") (field (name "PUBLISHER") "Altium Limited"))
      (libsource (lib "Miscellaneous Devices") (part "Res3"))
    )
    (comp (ref "R27")
      (value "Res3")
      (footprint "6-0805_N")
      (description "Resistor")
      (fields (field (name "ALTIUM_VALUE") "1kR") (field (name "PUBLISHER") "Altium Limited"))
      (libsource (lib "Miscellaneous Devices") (part "Res3"))
    )
    (comp (ref "R28")
      (value "Res3")
      (footprint "6-0805_N")
      (description "Resistor")
      (fields (field (name "ALTIUM_VALUE") "1K") (field (name "PUBLISHER") "Altium Limited"))
      (libsource (lib "Miscellaneous Devices") (part "Res3"))
    )
    (comp (ref "R29")
      (value "Res3")
      (footprint "6-0805_N")
      (description "Resistor")
      (fields (field (name "ALTIUM_VALUE") "4.7K") (field (name "PUBLISHER") "Altium Limited"))
      (libsource (lib "Miscellaneous Devices") (part "Res3"))
    )
    (comp (ref "R30")
      (value "Res3")
      (footprint "6-0805_N")
      (description "Resistor")
      (fields (field (name "ALTIUM_VALUE") "4.7K") (field (name "PUBLISHER") "Altium Limited"))
      (libsource (lib "Miscellaneous Devices") (part "Res3"))
    )
    (comp (ref "R31")
      (value "Res3")
      (footprint "6-0805_N")
      (description "Resistor")
      (fields (field (name "ALTIUM_VALUE") "470R") (field (name "PUBLISHER") "Altium Limited"))
      (libsource (lib "Miscellaneous Devices") (part "Res3"))
    )
    (comp (ref "R32")
      (value "Res3")
      (footprint "6-0805_N")
      (description "Resistor")
      (fields (field (name "ALTIUM_VALUE") "470R") (field (name "PUBLISHER") "Altium Limited"))
      (libsource (lib "Miscellaneous Devices") (part "Res3"))
    )
    (comp (ref "R33")
      (value "Res3")
      (footprint "6-0805_N")
      (description "Resistor")
      (fields (field (name "ALTIUM_VALUE") "1kR") (field (name "PUBLISHER") "Altium Limited"))
      (libsource (lib "Miscellaneous Devices") (part "Res3"))
    )
    (comp (ref "R34")
      (value "Res3")
      (footprint "6-0805_N")
      (description "Resistor")
      (fields (field (name "ALTIUM_VALUE") "500K") (field (name "PUBLISHER") "Altium Limited"))
      (libsource (lib "Miscellaneous Devices") (part "Res3"))
    )
    (comp (ref "R35")
      (value "Res3")
      (footprint "6-0805_N")
      (description "Resistor")
      (fields (field (name "ALTIUM_VALUE") "500K") (field (name "PUBLISHER") "Altium Limited"))
      (libsource (lib "Miscellaneous Devices") (part "Res3"))
    )
    (comp (ref "R36")
      (value "Res3")
      (footprint "6-0805_N")
      (description "Resistor")
      (fields (field (name "ALTIUM_VALUE") "1kR") (field (name "PUBLISHER") "Altium Limited"))
      (libsource (lib "Miscellaneous Devices") (part "Res3"))
    )
    (comp (ref "R37")
      (value "Res3")
      (footprint "6-0805_N")
      (description "Resistor")
      (fields (field (name "ALTIUM_VALUE") "1K") (field (name "PUBLISHER") "Altium Limited"))
      (libsource (lib "Miscellaneous Devices") (part "Res3"))
    )
    (comp (ref "R38")
      (value "Res3")
      (footprint "6-0805_N")
      (description "Resistor")
      (fields (field (name "ALTIUM_VALUE") "500K") (field (name "PUBLISHER") "Altium Limited"))
      (libsource (lib "Miscellaneous Devices") (part "Res3"))
    )
    (comp (ref "R39")
      (value "Res3")
      (footprint "6-0805_N")
      (description "Resistor")
      (fields (field (name "ALTIUM_VALUE") "500K") (field (name "PUBLISHER") "Altium Limited"))
      (libsource (lib "Miscellaneous Devices") (part "Res3"))
    )
    (comp (ref "R40")
      (value "Res3")
      (footprint "6-0805_N")
      (description "Resistor")
      (fields (field (name "ALTIUM_VALUE") "470R") (field (name "PUBLISHER") "Altium Limited"))
      (libsource (lib "Miscellaneous Devices") (part "Res3"))
    )
    (comp (ref "R41")
      (value "Res3")
      (footprint "6-0805_N")
      (description "Resistor")
      (fields (field (name "ALTIUM_VALUE") "1kR") (field (name "PUBLISHER") "Altium Limited"))
      (libsource (lib "Miscellaneous Devices") (part "Res3"))
    )
    (comp (ref "R42")
      (value "Res3")
      (footprint "6-0805_N")
      (description "Resistor")
      (fields (field (name "ALTIUM_VALUE") "60K") (field (name "PUBLISHER") "Altium Limited"))
      (libsource (lib "Miscellaneous Devices") (part "Res3"))
    )
    (comp (ref "R43")
      (value "Res3")
      (footprint "6-0805_N")
      (description "Resistor")
      (fields (field (name "ALTIUM_VALUE") "100k") (field (name "PUBLISHER") "Altium Limited"))
      (libsource (lib "Miscellaneous Devices") (part "Res3"))
    )
    (comp (ref "R44")
      (value "Res3")
      (footprint "6-0805_N")
      (description "Resistor")
      (fields (field (name "ALTIUM_VALUE") "1K") (field (name "PUBLISHER") "Altium Limited"))
      (libsource (lib "Miscellaneous Devices") (part "Res3"))
    )
    (comp (ref "R45")
      (value "Res3")
      (footprint "6-0805_N")
      (description "Resistor")
      (fields (field (name "ALTIUM_VALUE") "1K") (field (name "PUBLISHER") "Altium Limited"))
      (libsource (lib "Miscellaneous Devices") (part "Res3"))
    )
    (comp (ref "R46")
      (value "Res3")
      (footprint "6-0805_N")
      (description "Resistor")
      (fields (field (name "ALTIUM_VALUE") "150K") (field (name "PUBLISHER") "Altium Limited"))
      (libsource (lib "Miscellaneous Devices") (part "Res3"))
    )
    (comp (ref "R47")
      (value "Res3")
      (footprint "6-0805_N")
      (description "Resistor")
      (fields (field (name "ALTIUM_VALUE") "1k") (field (name "PUBLISHER") "Altium Limited"))
      (libsource (lib "Miscellaneous Devices") (part "Res3"))
    )
    (comp (ref "R48")
      (value "AT24C02")
      (footprint "SOP8_TDA2822")
      (libsource (lib "Simon'Library") (part "AT24C02"))
    )
    (comp (ref "R49")
      (value "Res3")
      (footprint "6-0805_N")
      (description "Resistor")
      (fields (field (name "ALTIUM_VALUE") "470R") (field (name "PUBLISHER") "Altium Limited"))
      (libsource (lib "Miscellaneous Devices") (part "Res3"))
    )
    (comp (ref "R50")
      (value "Res3")
      (footprint "6-0805_N")
      (description "Resistor")
      (fields (field (name "ALTIUM_VALUE") "1kR") (field (name "PUBLISHER") "Altium Limited"))
      (libsource (lib "Miscellaneous Devices") (part "Res3"))
    )
    (comp (ref "R51")
      (value "Res3")
      (footprint "6-0805_N")
      (description "Resistor")
      (fields (field (name "ALTIUM_VALUE") "60K") (field (name "PUBLISHER") "Altium Limited"))
      (libsource (lib "Miscellaneous Devices") (part "Res3"))
    )
    (comp (ref "R52")
      (value "Res3")
      (footprint "6-0805_N")
      (description "Resistor")
      (fields (field (name "ALTIUM_VALUE") "1K") (field (name "PUBLISHER") "Altium Limited"))
      (libsource (lib "Miscellaneous Devices") (part "Res3"))
    )
    (comp (ref "R53")
      (value "Res3")
      (footprint "6-0805_N")
      (description "Resistor")
      (fields (field (name "ALTIUM_VALUE") "1K") (field (name "PUBLISHER") "Altium Limited"))
      (libsource (lib "Miscellaneous Devices") (part "Res3"))
    )
    (comp (ref "R54")
      (value "Res3")
      (footprint "6-0805_N")
      (description "Resistor")
      (fields (field (name "ALTIUM_VALUE") "100k") (field (name "PUBLISHER") "Altium Limited"))
      (libsource (lib "Miscellaneous Devices") (part "Res3"))
    )
    (comp (ref "R55")
      (value "Res3")
      (footprint "6-0805_N")
      (description "Resistor")
      (fields (field (name "ALTIUM_VALUE") "1k") (field (name "PUBLISHER") "Altium Limited"))
      (libsource (lib "Miscellaneous Devices") (part "Res3"))
    )
    (comp (ref "R56")
      (value "Res3")
      (footprint "6-0805_N")
      (description "Resistor")
      (fields (field (name "ALTIUM_VALUE") "0R") (field (name "PUBLISHER") "Altium Limited"))
      (libsource (lib "Miscellaneous Devices") (part "Res3"))
    )
    (comp (ref "R57")
      (value "Res3")
      (footprint "6-0805_N")
      (description "Resistor")
      (fields (field (name "ALTIUM_VALUE") "10k") (field (name "PUBLISHER") "Altium Limited"))
      (libsource (lib "Miscellaneous Devices") (part "Res3"))
    )
    (comp (ref "R58")
      (value "Res3")
      (footprint "6-0805_N")
      (description "Resistor")
      (fields (field (name "ALTIUM_VALUE") "470R") (field (name "PUBLISHER") "Altium Limited"))
      (libsource (lib "Miscellaneous Devices") (part "Res3"))
    )
    (comp (ref "R59")
      (value "Res3")
      (footprint "6-0805_N")
      (description "Resistor")
      (fields (field (name "ALTIUM_VALUE") "1kR") (field (name "PUBLISHER") "Altium Limited"))
      (libsource (lib "Miscellaneous Devices") (part "Res3"))
    )
    (comp (ref "R60")
      (value "Res_Pack_100R")
      (footprint "Res_Pack_0603")
      (description "Res_Pack_4")
      (libsource (lib "Simon'Library") (part "Res_Pack_4"))
    )
    (comp (ref "R61")
      (value "Res_Pack_100R")
      (footprint "Res_Pack_0603")
      (description "Res_Pack_4")
      (libsource (lib "Simon'Library") (part "Res_Pack_4"))
    )
    (comp (ref "R62")
      (value "Res3")
      (footprint "6-0805_N")
      (description "Resistor")
      (fields (field (name "ALTIUM_VALUE") "1K") (field (name "PUBLISHER") "Altium Limited"))
      (libsource (lib "Miscellaneous Devices") (part "Res3"))
    )
    (comp (ref "R63")
      (value "Res3")
      (footprint "6-0805_N")
      (description "Resistor")
      (fields (field (name "ALTIUM_VALUE") "1k") (field (name "PUBLISHER") "Altium Limited"))
      (libsource (lib "Miscellaneous Devices") (part "Res3"))
    )
    (comp (ref "R64")
      (value "Res3")
      (footprint "6-0805_N")
      (description "Resistor")
      (fields (field (name "ALTIUM_VALUE") "0R") (field (name "PUBLISHER") "Altium Limited"))
      (libsource (lib "Miscellaneous Devices") (part "Res3"))
    )
    (comp (ref "S1")
      (value "SW DIP-8")
      (footprint "DHN(F)_8Pin")
      (description "DIP Switch, 8 Position, SPST")
      (fields (field (name "PUBLISHER") "Altium Limited"))
      (libsource (lib "Miscellaneous Devices") (part "SW DIP-8"))
    )
    (comp (ref "S2")
      (value "Reset")
      (footprint "SWP_PB_6.5mm")
      (description "Switch")
      (fields (field (name "PUBLISHER") "Altium Limited"))
      (libsource (lib "Miscellaneous Devices") (part "SW-PB"))
    )
    (comp (ref "U1") (value "MQ_Alcohol") (footprint "MQ") (libsource (lib "Simon'Library") (part "MQ")))
    (comp (ref "U2")
      (value "M62429")
      (footprint "SO8_N")
      (description "Digital Adjust Res")
      (libsource (lib "Simon'Library") (part "M62429"))
    )
    (comp (ref "U3")
      (value "LM2576SX-5.0")
      (footprint "TS5B_L")
      (description "SIMPLE SWITCHER® 3A Step-Down Voltage Regulator, 5-pin TO-263")
      (fields (field (name "MANUFACTURER") "National Semiconductor"))
      (libsource (lib "Altium Content Vault") (part "PM-REG-LM2575HVS-12"))
    )
    (comp (ref "U4")
      (value "AMS1117")
      (footprint "SOT223_N")
      (libsource (lib "Simon'Library") (part "AMS1117"))
    )
    (comp (ref "U5")
      (value "ESP-07")
      (footprint "ESP-07_Wifi")
      (libsource (lib "Simon'Library") (part "ESP-07_Wifi"))
    )
    (comp (ref "U6")
      (value "LM2904M")
      (footprint "D0008A_M")
      (description "Low Power Dual Operational Amplifier, 8-pin Narrow SOIC")
      (fields (field (name "MANUFACTURER") "Texas Instruments"))
      (libsource (lib "Altium Content Vault") (part "AMP-OPA-LM158-8"))
    )
    (comp (ref "U7")
      (value "DS18B20")
      (footprint "TO-92A")
      (libsource (lib "Simon'Library") (part "DS18B20"))
    )
    (comp (ref "U8")
      (value "MMA8452Q")
      (footprint "QFN-16")
      (libsource (lib "Simon'Library") (part "MMA8452Q"))
    )
    (comp (ref "U9")
      (value "LM2904M")
      (footprint "D0008A_M")
      (description "Low Power Dual Operational Amplifier, 8-pin Narrow SOIC")
      (fields (field (name "MANUFACTURER") "Texas Instruments"))
      (libsource (lib "Altium Content Vault") (part "AMP-OPA-LM158-8"))
    )
    (comp (ref "U10")
      (value "STM32F103RCT6")
      (footprint "LQFP64_L")
      (libsource (lib "Altium Content Vault") (part "MC-ARM-STM32F101-SQ64"))
    )
    (comp (ref "U11")
      (value "LM358AMX")
      (footprint "M08A_M")
      (description "Low Power Dual Operational Amplifier, 8-pin Narrow SOIC")
      (fields (field (name "MANUFACTURER") "National Semiconductor"))
      (libsource (lib "Altium Content Vault") (part "AMP-OPA-LM158-8"))
    )
    (comp (ref "U12")
      (value "LM2904M")
      (footprint "D0008A_M")
      (description "Low Power Dual Operational Amplifier, 8-pin Narrow SOIC")
      (fields (field (name "MANUFACTURER") "Texas Instruments"))
      (libsource (lib "Altium Content Vault") (part "AMP-OPA-LM158-8"))
    )
    (comp (ref "U13")
      (value "KP10104CTLD")
      (footprint "KP10104CTLD")
      (description "4-Pin Phototransistor Optocoupler")
      (fields (field (name "PUBLISHER") "Altium Limited"))
      (libsource (lib "Miscellaneous Devices") (part "Optoisolator1"))
    )
    (comp (ref "U14")
      (value "KP10104CTLD")
      (footprint "KP10104CTLD")
      (description "4-Pin Phototransistor Optocoupler")
      (fields (field (name "PUBLISHER") "Altium Limited"))
      (libsource (lib "Miscellaneous Devices") (part "Optoisolator1"))
    )
    (comp (ref "U15")
      (value "KP10104CTLD")
      (footprint "KP10104CTLD")
      (description "4-Pin Phototransistor Optocoupler")
      (fields (field (name "PUBLISHER") "Altium Limited"))
      (libsource (lib "Miscellaneous Devices") (part "Optoisolator1"))
    )
    (comp (ref "U16")
      (value "KP10104CTLD")
      (footprint "KP10104CTLD")
      (description "4-Pin Phototransistor Optocoupler")
      (fields (field (name "PUBLISHER") "Altium Limited"))
      (libsource (lib "Miscellaneous Devices") (part "Optoisolator1"))
    )
    (comp (ref "U17")
      (value "CS8508E")
      (footprint "SO8_L")
      (description "Audio Amplifier")
      (libsource (lib "Simon'Library") (part "CS8508E"))
    )
    (comp (ref "Y1")
      (value "XTAL")
      (footprint "OSC_5032_2Pin")
      (description "Crystal Oscillator")
      (fields (field (name "PUBLISHER") "Altium Limited"))
      (libsource (lib "Miscellaneous Devices") (part "XTAL"))
    )
  )
  (nets
    (net (code "1") (name "+3.3V") (class "Default")
      (node (ref "C10") (pin "1") (pinfunction "1_1") (pintype "passive"))
      (node (ref "C11") (pin "1") (pinfunction "1_1") (pintype "passive"))
      (node (ref "C13") (pin "1") (pinfunction "1_1") (pintype "passive"))
      (node (ref "C14") (pin "1") (pinfunction "1_1") (pintype "passive"))
      (node (ref "C18") (pin "2") (pinfunction "2_2") (pintype "passive"))
      (node (ref "C19") (pin "2") (pinfunction "2_2") (pintype "passive"))
      (node (ref "C27") (pin "2") (pinfunction "2_2") (pintype "passive"))
      (node (ref "C28") (pin "2") (pinfunction "2_2") (pintype "passive"))
      (node (ref "C37") (pin "1") (pinfunction "1_1") (pintype "passive"))
      (node (ref "C38") (pin "1") (pinfunction "1_1") (pintype "passive"))
      (node (ref "C43") (pin "1") (pinfunction "1_1") (pintype "passive"))
      (node (ref "C44") (pin "1") (pinfunction "1_1") (pintype "passive"))
      (node (ref "P12") (pin "1") (pinfunction "1_1") (pintype "passive"))
      (node (ref "R11") (pin "2") (pinfunction "2_2") (pintype "passive"))
      (node (ref "R15") (pin "2") (pinfunction "2_2") (pintype "passive"))
      (node (ref "R19") (pin "2") (pinfunction "2_2") (pintype "passive"))
      (node (ref "R24") (pin "2") (pinfunction "2_2") (pintype "passive"))
      (node (ref "R25") (pin "2") (pinfunction "2_2") (pintype "passive"))
      (node (ref "R29") (pin "2") (pinfunction "2_2") (pintype "passive"))
      (node (ref "R30") (pin "2") (pinfunction "2_2") (pintype "passive"))
      (node (ref "R34") (pin "2") (pinfunction "2_2") (pintype "passive"))
      (node (ref "R35") (pin "2") (pinfunction "2_2") (pintype "passive"))
      (node (ref "R38") (pin "2") (pinfunction "2_2") (pintype "passive"))
      (node (ref "R39") (pin "2") (pinfunction "2_2") (pintype "passive"))
      (node (ref "R48") (pin "8") (pinfunction "VCC_8") (pintype "passive"))
      (node (ref "R57") (pin "1") (pinfunction "1_1") (pintype "passive"))
      (node (ref "R6") (pin "2") (pinfunction "2_2") (pintype "passive"))
      (node (ref "R64") (pin "1") (pinfunction "1_1") (pintype "passive"))
      (node (ref "U10") (pin "13") (pinfunction "VDDA_13") (pintype "power_in"))
      (node (ref "U10") (pin "19") (pinfunction "VDD_4_19") (pintype "power_in"))
      (node (ref "U10") (pin "32") (pinfunction "VDD_1_32") (pintype "power_in"))
      (node (ref "U10") (pin "48") (pinfunction "VDD_2_48") (pintype "power_in"))
      (node (ref "U10") (pin "64") (pinfunction "VDD_3_64") (pintype "power_in"))
      (node (ref "U4") (pin "4") (pinfunction "Vout_4") (pintype "passive"))
      (node (ref "U5") (pin "1") (pinfunction "RST_1") (pintype "passive"))
      (node (ref "U5") (pin "8") (pinfunction "VCC_8") (pintype "passive"))
      (node (ref "U7") (pin "3") (pinfunction "VDD_3") (pintype "passive"))
      (node (ref "U8") (pin "1") (pinfunction "VDDIO_1") (pintype "passive"))
      (node (ref "U8") (pin "14") (pinfunction "VDD_14") (pintype "passive"))
    )
    (net (code "2") (name "+5V") (class "Default")
      (node (ref "C3") (pin "2") (pinfunction "2_2") (pintype "passive"))
      (node (ref "C45") (pin "1") (pinfunction "1_1") (pintype "passive"))
      (node (ref "C46") (pin "1") (pinfunction "1_1") (pintype "passive"))
      (node (ref "C47") (pin "1") (pinfunction "1_1") (pintype "passive"))
      (node (ref "C49") (pin "1") (pinfunction "1_1") (pintype "passive"))
      (node (ref "C50") (pin "1") (pinfunction "1_1") (pintype "passive"))
      (node (ref "C6") (pin "1") (pinfunction "1_1") (pintype "passive"))
      (node (ref "D12") (pin "2") (pinfunction "K_2") (pintype "passive"))
      (node (ref "D14") (pin "2") (pinfunction "K_2") (pintype "passive"))
      (node (ref "D16") (pin "2") (pinfunction "K_2") (pintype "passive"))
      (node (ref "D6") (pin "2") (pinfunction "K_2") (pintype "passive"))
      (node (ref "D8") (pin "2") (pinfunction "K_2") (pintype "passive"))
      (node (ref "D9") (pin "2") (pinfunction "K_2") (pintype "passive"))
      (node (ref "L2") (pin "2") (pinfunction "2_2") (pintype "passive"))
      (node (ref "L3") (pin "2") (pinfunction "2_2") (pintype "passive"))
      (node (ref "LS1") (pin "1") (pinfunction "1_1") (pintype "passive"))
      (node (ref "P13") (pin "1") (pinfunction "1_1") (pintype "passive"))
      (node (ref "P7") (pin "1") (pinfunction "1_1") (pintype "passive"))
      (node (ref "P8") (pin "10") (pinfunction "VDD_10") (pintype "passive"))
      (node (ref "R1") (pin "1") (pinfunction "1_1") (pintype "passive"))
      (node (ref "R10") (pin "1") (pinfunction "1_1") (pintype "passive"))
      (node (ref "R13") (pin "1") (pinfunction "1_1") (pintype "passive"))
      (node (ref "R17") (pin "1") (pinfunction "1_1") (pintype "passive"))
      (node (ref "U1") (pin "1") (pinfunction "A_1") (pintype "passive"))
      (node (ref "U1") (pin "2") (pinfunction "H_2") (pintype "passive"))
      (node (ref "U11") (pin "8") (pinfunction "V+_8") (pintype "power_in"))
      (node (ref "U12") (pin "8") (pinfunction "V+_8") (pintype "power_in"))
      (node (ref "U16") (pin "1") (pinfunction "A_1") (pintype "passive"))
      (node (ref "U17") (pin "5") (pinfunction "VDD_5") (pintype "passive"))
      (node (ref "U4") (pin "3") (pinfunction "Vin_3") (pintype "passive"))
      (node (ref "U6") (pin "8") (pinfunction "V+_8") (pintype "power_in"))
      (node (ref "U9") (pin "8") (pinfunction "V+_8") (pintype "power_in"))
    )
    (net (code "3") (name "+12V") (class "Default")
      (node (ref "C12") (pin "1") (pinfunction "1_1") (pintype "passive"))
      (node (ref "C4") (pin "1") (pinfunction "1_1") (pintype "passive"))
      (node (ref "C5") (pin "1") (pinfunction "1_1") (pintype "passive"))
      (node (ref "C7") (pin "1") (pinfunction "1_1") (pintype "passive"))
      (node (ref "C9") (pin "1") (pinfunction "1_1") (pintype "passive"))
      (node (ref "CB1") (pin "2") (pinfunction "2_2") (pintype "passive"))
      (node (ref "D1") (pin "2") (pinfunction "K_2") (pintype "passive"))
      (node (ref "D3") (pin "2") (pinfunction "K_2") (pintype "passive"))
      (node (ref "D5") (pin "2") (pinfunction "K_2") (pintype "passive"))
      (node (ref "P2") (pin "1") (pinfunction "1_1") (pintype "passive"))
      (node (ref "P4") (pin "1") (pinfunction "1_1") (pintype "passive"))
      (node (ref "P6") (pin "1") (pinfunction "1_1") (pintype "passive"))
      (node (ref "P9") (pin "1") (pinfunction "1_1") (pintype "passive"))
      (node (ref "R4") (pin "2") (pinfunction "2_2") (pintype "passive"))
      (node (ref "U3") (pin "1") (pinfunction "VIN_1") (pintype "power_in"))
    )
    (net (code "4") (name "/ADS_IN") (class "Default")
      (node (ref "C26") (pin "2") (pinfunction "2_2") (pintype "passive"))
      (node (ref "D11") (pin "2") (pinfunction "K_2") (pintype "passive"))
      (node (ref "D9") (pin "1") (pinfunction "A_1") (pintype "passive"))
      (node (ref "R32") (pin "1") (pinfunction "1_1") (pintype "passive"))
      (node (ref "U10") (pin "50") (pinfunction "PA15_50") (pintype "bidirectional"))
    )
    (net (code "5") (name "/ADS_OUT") (class "Default")
      (node (ref "C24") (pin "2") (pinfunction "2_2") (pintype "passive"))
      (node (ref "P5") (pin "1") (pinfunction "1_1") (pintype "passive"))
      (node (ref "R36") (pin "2") (pinfunction "2_2") (pintype "passive"))
      (node (ref "R64") (pin "2") (pinfunction "2_2") (pintype "passive"))
    )
    (net (code "6") (name "/AD_IN") (class "Default")
      (node (ref "C17") (pin "2") (pinfunction "2_2") (pintype "passive"))
      (node (ref "D6") (pin "1") (pinfunction "A_1") (pintype "passive"))
      (node (ref "D7") (pin "2") (pinfunction "K_2") (pintype "passive"))
      (node (ref "R26") (pin "1") (pinfunction "1_1") (pintype "passive"))
      (node (ref "U10") (pin "17") (pinfunction "PA3_17") (pintype "bidirectional"))
    )
    (net (code "7") (name "/AD_OUT") (class "Default")
      (node (ref "C15") (pin "2") (pinfunction "2_2") (pintype "passive"))
      (node (ref "P5") (pin "2") (pinfunction "2_2") (pintype "passive"))
      (node (ref "R27") (pin "2") (pinfunction "2_2") (pintype "passive"))
    )
    (net (code "8") (name "/AUDIO") (class "Default")
      (node (ref "C1") (pin "1") (pinfunction "1_1") (pintype "passive"))
      (node (ref "U10") (pin "20") (pinfunction "PA4_20") (pintype "bidirectional"))
    )
    (net (code "9") (name "/Alcohol_C") (class "Default")
      (node (ref "R5") (pin "1") (pinfunction "1_1") (pintype "passive"))
      (node (ref "U1") (pin "6") (pinfunction "B_6") (pintype "passive"))
      (node (ref "U10") (pin "24") (pinfunction "PC4_24") (pintype "bidirectional"))
    )
    (net (code "10") (name "/Bee") (class "Default")
      (node (ref "R14") (pin "2") (pinfunction "2_2") (pintype "passive"))
      (node (ref "U10") (pin "38") (pinfunction "PC7_38") (pintype "bidirectional"))
    )
    (net (code "11") (name "/CS_SD") (class "Default")
      (node (ref "R2") (pin "1") (pinfunction "1_1") (pintype "passive"))
      (node (ref "U10") (pin "55") (pinfunction "PB3_55") (pintype "bidirectional"))
    )
    (net (code "12") (name "/Debug_Rx") (class "Default")
      (node (ref "R63") (pin "2") (pinfunction "2_2") (pintype "passive"))
      (node (ref "U10") (pin "43") (pinfunction "PA10_43") (pintype "bidirectional"))
    )
    (net (code "13") (name "/Debug_Tx") (class "Default")
      (node (ref "R56") (pin "2") (pinfunction "2_2") (pintype "passive"))
      (node (ref "U10") (pin "42") (pinfunction "PA9_42") (pintype "bidirectional"))
    )
    (net (code "14") (name "/E2_SCL") (class "Default")
      (node (ref "R48") (pin "6") (pinfunction "SCL_6") (pintype "passive"))
      (node (ref "U10") (pin "25") (pinfunction "PC5_25") (pintype "bidirectional"))
    )
    (net (code "15") (name "/E2_SDA") (class "Default")
      (node (ref "R48") (pin "5") (pinfunction "SDA_5") (pintype "passive"))
      (node (ref "U10") (pin "26") (pinfunction "PB0_26") (pintype "bidirectional"))
    )
    (net (code "16") (name "/FHD_IN") (class "Default")
      (node (ref "C31") (pin "2") (pinfunction "2_2") (pintype "passive"))
      (node (ref "D12") (pin "1") (pinfunction "A_1") (pintype "passive"))
      (node (ref "D13") (pin "2") (pinfunction "K_2") (pintype "passive"))
      (node (ref "R40") (pin "1") (pinfunction "1_1") (pintype "passive"))
      (node (ref "U10") (pin "14") (pinfunction "PA0-WKUP_14") (pintype "bidirectional"))
    )
    (net (code "17") (name "/FHD_OUT") (class "Default")
      (node (ref "C19") (pin "1") (pinfunction "1_1") (pintype "passive"))
      (node (ref "C29") (pin "2") (pinfunction "2_2") (pintype "passive"))
      (node (ref "P10") (pin "1") (pinfunction "1_1") (pintype "passive"))
      (node (ref "R35") (pin "1") (pinfunction "1_1") (pintype "passive"))
      (node (ref "R41") (pin "2") (pinfunction "2_2") (pintype "passive"))
    )
    (net (code "18") (name "/FLD_IN") (class "Default")
      (node (ref "C23") (pin "2") (pinfunction "2_2") (pintype "passive"))
      (node (ref "D10") (pin "2") (pinfunction "K_2") (pintype "passive"))
      (node (ref "D8") (pin "1") (pinfunction "A_1") (pintype "passive"))
      (node (ref "R31") (pin "1") (pinfunction "1_1") (pintype "passive"))
      (node (ref "U10") (pin "11") (pinfunction "PC3_11") (pintype "bidirectional"))
    )
    (net (code "19") (name "/FLD_OUT") (class "Default")
      (node (ref "C18") (pin "1") (pinfunction "1_1") (pintype "passive"))
      (node (ref "C21") (pin "2") (pinfunction "2_2") (pintype "passive"))
      (node (ref "P10") (pin "2") (pinfunction "2_2") (pintype "passive"))
      (node (ref "R33") (pin "2") (pinfunction "2_2") (pintype "passive"))
      (node (ref "R34") (pin "1") (pinfunction "1_1") (pintype "passive"))
    )
    (net (code "20") (name "/Fan") (class "Default")
      (node (ref "R15") (pin "1") (pinfunction "1_1") (pintype "passive"))
      (node (ref "R16") (pin "1") (pinfunction "1_1") (pintype "passive"))
      (node (ref "R43") (pin "2") (pinfunction "2_2") (pintype "passive"))
      (node (ref "U10") (pin "28") (pinfunction "PB2_28") (pintype "bidirectional"))
    )
    (net (code "21") (name "/Fire_Tem_D") (class "Default")
      (node (ref "R42") (pin "2") (pinfunction "2_2") (pintype "passive"))
      (node (ref "U10") (pin "8") (pinfunction "PC0_8") (pintype "bidirectional"))
      (node (ref "U11") (pin "1") (pinfunction "OUTA_1") (pintype "output"))
    )
    (net (code "22") (name "/Fire_Tem_T") (class "Default")
      (node (ref "R51") (pin "2") (pinfunction "2_2") (pintype "passive"))
      (node (ref "U10") (pin "9") (pinfunction "PC1_9") (pintype "bidirectional"))
      (node (ref "U11") (pin "7") (pinfunction "OUTB_7") (pintype "output"))
    )
    (net (code "23") (name "/Fire_UP") (class "Default")
      (node (ref "R11") (pin "1") (pinfunction "1_1") (pintype "passive"))
      (node (ref "R12") (pin "1") (pinfunction "1_1") (pintype "passive"))
      (node (ref "U10") (pin "10") (pinfunction "PC2_10") (pintype "bidirectional"))
    )
    (net (code "24") (name "/IO1") (class "Default")
      (node (ref "R61") (pin "1") (pinfunction "1_1") (pintype "passive"))
      (node (ref "U10") (pin "58") (pinfunction "PB6_58") (pintype "bidirectional"))
    )
    (net (code "25") (name "/IO2") (class "Default")
      (node (ref "R61") (pin "2") (pinfunction "2_2") (pintype "passive"))
      (node (ref "U10") (pin "59") (pinfunction "PB7_59") (pintype "bidirectional"))
    )
    (net (code "26") (name "/IO3") (class "Default")
      (node (ref "R61") (pin "3") (pinfunction "3_3") (pintype "passive"))
      (node (ref "U10") (pin "61") (pinfunction "PB8_61") (pintype "bidirectional"))
    )
    (net (code "27") (name "/IO4") (class "Default")
      (node (ref "R61") (pin "4") (pinfunction "4_4") (pintype "passive"))
      (node (ref "U10") (pin "62") (pinfunction "PB9_62") (pintype "bidirectional"))
    )
    (net (code "28") (name "/LDHD_IN") (class "Default")
      (node (ref "C42") (pin "2") (pinfunction "2_2") (pintype "passive"))
      (node (ref "D16") (pin "1") (pinfunction "A_1") (pintype "passive"))
      (node (ref "D17") (pin "2") (pinfunction "K_2") (pintype "passive"))
      (node (ref "R58") (pin "1") (pinfunction "1_1") (pintype "passive"))
      (node (ref "U10") (pin "23") (pinfunction "PA7_23") (pintype "bidirectional"))
    )
    (net (code "29") (name "/LDHD_OUT") (class "Default")
      (node (ref "C28") (pin "1") (pinfunction "1_1") (pintype "passive"))
      (node (ref "C40") (pin "2") (pinfunction "2_2") (pintype "passive"))
      (node (ref "P11") (pin "1") (pinfunction "1_1") (pintype "passive"))
      (node (ref "R39") (pin "1") (pinfunction "1_1") (pintype "passive"))
      (node (ref "R59") (pin "2") (pinfunction "2_2") (pintype "passive"))
    )
    (net (code "30") (name "/LDLD_IN") (class "Default")
      (node (ref "C36") (pin "2") (pinfunction "2_2") (pintype "passive"))
      (node (ref "D14") (pin "1") (pinfunction "A_1") (pintype "passive"))
      (node (ref "D15") (pin "2") (pinfunction "K_2") (pintype "passive"))
      (node (ref "R49") (pin "1") (pinfunction "1_1") (pintype "passive"))
      (node (ref "U10") (pin "22") (pinfunction "PA6_22") (pintype "bidirectional"))
    )
    (net (code "31") (name "/LDLD_OUT") (class "Default")
      (node (ref "C27") (pin "1") (pinfunction "1_1") (pintype "passive"))
      (node (ref "C34") (pin "2") (pinfunction "2_2") (pintype "passive"))
      (node (ref "P11") (pin "2") (pinfunction "2_2") (pintype "passive"))
      (node (ref "R38") (pin "1") (pinfunction "1_1") (pintype "passive"))
      (node (ref "R50") (pin "2") (pinfunction "2_2") (pintype "passive"))
    )
    (net (code "32") (name "/M6_CLK") (class "Default")
      (node (ref "U10") (pin "41") (pinfunction "PA8_41") (pintype "bidirectional"))
      (node (ref "U2") (pin "5") (pinfunction "CLK_5") (pintype "passive"))
    )
    (net (code "33") (name "/M6_Data") (class "Default")
      (node (ref "U10") (pin "21") (pinfunction "PA5_21") (pintype "bidirectional"))
      (node (ref "U2") (pin "4") (pinfunction "DATA_4") (pintype "passive"))
    )
    (net (code "34") (name "/MMA_SCL") (class "Default")
      (node (ref "R29") (pin "1") (pinfunction "1_1") (pintype "passive"))
      (node (ref "U10") (pin "57") (pinfunction "PB5_57") (pintype "bidirectional"))
      (node (ref "U8") (pin "4") (pinfunction "SCL_4") (pintype "passive"))
    )
    (net (code "35") (name "/MMA_SDA") (class "Default")
      (node (ref "R30") (pin "1") (pinfunction "1_1") (pintype "passive"))
      (node (ref "U10") (pin "56") (pinfunction "PB4_56") (pintype "bidirectional"))
      (node (ref "U8") (pin "6") (pinfunction "SDA_6") (pintype "passive"))
    )
    (net (code "36") (name "/Pump1") (class "Default")
      (node (ref "R19") (pin "1") (pinfunction "1_1") (pintype "passive"))
      (node (ref "R22") (pin "1") (pinfunction "1_1") (pintype "passive"))
      (node (ref "U10") (pin "15") (pinfunction "PA1_15") (pintype "bidirectional"))
    )
    (net (code "37") (name "/Pump2") (class "Default")
      (node (ref "R6") (pin "1") (pinfunction "1_1") (pintype "passive"))
      (node (ref "R7") (pin "1") (pinfunction "1_1") (pintype "passive"))
      (node (ref "U10") (pin "16") (pinfunction "PA2_16") (pintype "bidirectional"))
    )
    (net (code "38") (name "/SR_D0") (class "Default")
      (node (ref "R20") (pin "2") (pinfunction "2_2") (pintype "passive"))
      (node (ref "U10") (pin "35") (pinfunction "PB14_35") (pintype "bidirectional"))
    )
    (net (code "39") (name "/SR_D1") (class "Default")
      (node (ref "R21") (pin "2") (pinfunction "2_2") (pintype "passive"))
      (node (ref "U10") (pin "36") (pinfunction "PB15_36") (pintype "bidirectional"))
    )
    (net (code "40") (name "/SR_D2") (class "Default")
      (node (ref "R23") (pin "2") (pinfunction "2_2") (pintype "passive"))
      (node (ref "U10") (pin "37") (pinfunction "PC6_37") (pintype "bidirectional"))
    )
    (net (code "41") (name "/SR_LED") (class "Default")
      (node (ref "R62") (pin "2") (pinfunction "2_2") (pintype "passive"))
      (node (ref "U10") (pin "33") (pinfunction "PB12_33") (pintype "bidirectional"))
    )
    (net (code "42") (name "/SR_SW") (class "Default")
      (node (ref "R18") (pin "2") (pinfunction "2_2") (pintype "passive"))
      (node (ref "U10") (pin "34") (pinfunction "PB13_34") (pintype "bidirectional"))
    )
    (net (code "43") (name "/SW1") (class "Default")
      (node (ref "S1") (pin "1") (pinfunction "A1_1") (pintype "passive"))
      (node (ref "U10") (pin "51") (pinfunction "PC10_51") (pintype "bidirectional"))
    )
    (net (code "44") (name "/SW2") (class "Default")
      (node (ref "S1") (pin "2") (pinfunction "A2_2") (pintype "passive"))
      (node (ref "U10") (pin "52") (pinfunction "PC11_52") (pintype "bidirectional"))
    )
    (net (code "45") (name "/SW3") (class "Default")
      (node (ref "S1") (pin "3") (pinfunction "A3_3") (pintype "passive"))
      (node (ref "U10") (pin "53") (pinfunction "PC12_53") (pintype "bidirectional"))
    )
    (net (code "46") (name "/SW4") (class "Default")
      (node (ref "S1") (pin "4") (pinfunction "A4_4") (pintype "passive"))
      (node (ref "U10") (pin "54") (pinfunction "PD2_54") (pintype "bidirectional"))
    )
    (net (code "47") (name "/SW5") (class "Default")
      (node (ref "S1") (pin "5") (pinfunction "A5_5") (pintype "passive"))
      (node (ref "U10") (pin "45") (pinfunction "PA12_45") (pintype "bidirectional"))
    )
    (net (code "48") (name "/SW6") (class "Default")
      (node (ref "S1") (pin "6") (pinfunction "A6_6") (pintype "passive"))
      (node (ref "U10") (pin "44") (pinfunction "PA11_44") (pintype "bidirectional"))
    )
    (net (code "49") (name "/SW7") (class "Default")
      (node (ref "S1") (pin "7") (pinfunction "A7_7") (pintype "passive"))
      (node (ref "U10") (pin "40") (pinfunction "PC9_40") (pintype "bidirectional"))
    )
    (net (code "50") (name "/SW8") (class "Default")
      (node (ref "S1") (pin "8") (pinfunction "A8_8") (pintype "passive"))
      (node (ref "U10") (pin "39") (pinfunction "PC8_39") (pintype "bidirectional"))
    )
    (net (code "51") (name "/SWCLK") (class "Default")
      (node (ref "R55") (pin "2") (pinfunction "2_2") (pintype "passive"))
      (node (ref "U10") (pin "49") (pinfunction "PA14_49") (pintype "bidirectional"))
    )
    (net (code "52") (name "/SWDIO") (class "Default")
      (node (ref "R47") (pin "2") (pinfunction "2_2") (pintype "passive"))
      (node (ref "U10") (pin "46") (pinfunction "PA13_46") (pintype "bidirectional"))
    )
    (net (code "53") (name "/Tem") (class "Default")
      (node (ref "R25") (pin "1") (pinfunction "1_1") (pintype "passive"))
      (node (ref "U10") (pin "27") (pinfunction "PB1_27") (pintype "bidirectional"))
      (node (ref "U7") (pin "2") (pinfunction "DQ_2") (pintype "passive"))
    )
    (net (code "54") (name "/WIFI_RX") (class "Default")
      (node (ref "U10") (pin "29") (pinfunction "PB10_29") (pintype "bidirectional"))
      (node (ref "U5") (pin "15") (pinfunction "RXD0_15") (pintype "passive"))
    )
    (net (code "55") (name "/WIFI_TX") (class "Default")
      (node (ref "U10") (pin "30") (pinfunction "PB11_30") (pintype "bidirectional"))
      (node (ref "U5") (pin "16") (pinfunction "TXD0_16") (pintype "passive"))
    )
    (net (code "56") (name "Net-(C2-Pad1)") (class "Default")
      (node (ref "C2") (pin "1") (pinfunction "1_1") (pintype "passive"))
      (node (ref "R46") (pin "1") (pinfunction "1_1") (pintype "passive"))
    )
    (net (code "57") (name "Net-(CB1-Pad1)") (class "Default")
      (node (ref "CB1") (pin "1") (pinfunction "1_1") (pintype "passive"))
      (node (ref "P1") (pin "1") (pinfunction "1_1") (pintype "passive"))
    )
    (net (code "58") (name "Net-(D1-A)") (class "Default")
      (node (ref "C4") (pin "2") (pinfunction "2_2") (pintype "passive"))
      (node (ref "C5") (pin "2") (pinfunction "2_2") (pintype "passive"))
      (node (ref "D1") (pin "1") (pinfunction "A_1") (pintype "passive"))
      (node (ref "P2") (pin "2") (pinfunction "2_2") (pintype "passive"))
      (node (ref "Q1") (pin "2") (pinfunction "D_2") (pintype "passive"))
    )
    (net (code "59") (name "Net-(D2-A)") (class "Default")
      (node (ref "D2") (pin "1") (pinfunction "A_1") (pintype "passive"))
      (node (ref "R4") (pin "1") (pinfunction "1_1") (pintype "passive"))
    )
    (net (code "60") (name "Net-(D3-A)") (class "Default")
      (node (ref "C9") (pin "2") (pinfunction "2_2") (pintype "passive"))
      (node (ref "D3") (pin "1") (pinfunction "A_1") (pintype "passive"))
      (node (ref "P6") (pin "2") (pinfunction "2_2") (pintype "passive"))
      (node (ref "Q6") (pin "2") (pinfunction "D_2") (pintype "passive"))
    )
    (net (code "61") (name "Net-(D4-K)") (class "Default")
      (node (ref "D4") (pin "2") (pinfunction "K_2") (pintype "passive"))
      (node (ref "L1") (pin "1") (pinfunction "1_1") (pintype "passive"))
      (node (ref "U3") (pin "2") (pinfunction "OUT_2") (pintype "power_in"))
    )
    (net (code "62") (name "Net-(D5-A)") (class "Default")
      (node (ref "C12") (pin "2") (pinfunction "2_2") (pintype "passive"))
      (node (ref "D5") (pin "1") (pinfunction "A_1") (pintype "passive"))
      (node (ref "P9") (pin "2") (pinfunction "2_2") (pintype "passive"))
      (node (ref "Q8") (pin "2") (pinfunction "D_2") (pintype "passive"))
    )
    (net (code "63") (name "Net-(P7-Pad2)") (class "Default")
      (node (ref "P7") (pin "2") (pinfunction "2_2") (pintype "passive"))
      (node (ref "R60") (pin "8") (pinfunction "8_8") (pintype "passive"))
    )
    (net (code "64") (name "Net-(P7-Pad3)") (class "Default")
      (node (ref "P7") (pin "3") (pinfunction "3_3") (pintype "passive"))
      (node (ref "R60") (pin "7") (pinfunction "7_7") (pintype "passive"))
    )
    (net (code "65") (name "Net-(P7-Pad4)") (class "Default")
      (node (ref "P7") (pin "4") (pinfunction "4_4") (pintype "passive"))
      (node (ref "R60") (pin "6") (pinfunction "6_6") (pintype "passive"))
    )
    (net (code "66") (name "Net-(P7-Pad5)") (class "Default")
      (node (ref "P7") (pin "5") (pinfunction "5_5") (pintype "passive"))
      (node (ref "R60") (pin "5") (pinfunction "5_5") (pintype "passive"))
    )
    (net (code "67") (name "Net-(P8-D0)") (class "Default")
      (node (ref "P8") (pin "6") (pinfunction "D0_6") (pintype "passive"))
      (node (ref "R20") (pin "1") (pinfunction "1_1") (pintype "passive"))
    )
    (net (code "68") (name "Net-(P8-D1)") (class "Default")
      (node (ref "P8") (pin "7") (pinfunction "D1_7") (pintype "passive"))
      (node (ref "R21") (pin "1") (pinfunction "1_1") (pintype "passive"))
    )
    (net (code "69") (name "Net-(P8-D2)") (class "Default")
      (node (ref "P8") (pin "8") (pinfunction "D2_8") (pintype "passive"))
      (node (ref "R23") (pin "1") (pinfunction "1_1") (pintype "passive"))
    )
    (net (code "70") (name "Net-(P8-LED)") (class "Default")
      (node (ref "P8") (pin "3") (pinfunction "LED_3") (pintype "passive"))
      (node (ref "R62") (pin "1") (pinfunction "1_1") (pintype "passive"))
    )
    (net (code "71") (name "Net-(P8-SW)") (class "Default")
      (node (ref "P8") (pin "4") (pinfunction "SW_4") (pintype "passive"))
      (node (ref "R18") (pin "1") (pinfunction "1_1") (pintype "passive"))
    )
    (net (code "72") (name "Net-(P12-Pad2)") (class "Default")
      (node (ref "P12") (pin "2") (pinfunction "2_2") (pintype "passive"))
      (node (ref "R47") (pin "1") (pinfunction "1_1") (pintype "passive"))
    )
    (net (code "73") (name "Net-(P12-Pad3)") (class "Default")
      (node (ref "P12") (pin "3") (pinfunction "3_3") (pintype "passive"))
      (node (ref "R55") (pin "1") (pinfunction "1_1") (pintype "passive"))
    )
    (net (code "74") (name "Net-(P13-Pad2)") (class "Default")
      (node (ref "P13") (pin "2") (pinfunction "2_2") (pintype "passive"))
      (node (ref "R56") (pin "1") (pinfunction "1_1") (pintype "passive"))
    )
    (net (code "75") (name "Net-(P13-Pad3)") (class "Default")
      (node (ref "P13") (pin "3") (pinfunction "3_3") (pintype "passive"))
      (node (ref "R63") (pin "1") (pinfunction "1_1") (pintype "passive"))
    )
    (net (code "76") (name "Net-(P14-Pad1)") (class "Default")
      (node (ref "P14") (pin "1") (pinfunction "1_1") (pintype "passive"))
      (node (ref "R44") (pin "1") (pinfunction "1_1") (pintype "passive"))
    )
    (net (code "77") (name "Net-(P15-Pad1)") (class "Default")
      (node (ref "P15") (pin "1") (pinfunction "1_1") (pintype "passive"))
      (node (ref "R52") (pin "1") (pinfunction "1_1") (pintype "passive"))
    )
    (net (code "78") (name "Net-(Q1-G)") (class "Default")
      (node (ref "Q1") (pin "1") (pinfunction "G_1") (pintype "passive"))
      (node (ref "Q2") (pin "3") (pinfunction "C_3") (pintype "passive"))
      (node (ref "R1") (pin "2") (pinfunction "2_2") (pintype "passive"))
    )
    (net (code "79") (name "Net-(Q2-B)") (class "Default")
      (node (ref "Q2") (pin "1") (pinfunction "B_1") (pintype "passive"))
      (node (ref "R7") (pin "2") (pinfunction "2_2") (pintype "passive"))
    )
    (net (code "80") (name "Net-(Q3-D)") (class "Default")
      (node (ref "P4") (pin "2") (pinfunction "2_2") (pintype "passive"))
      (node (ref "Q3") (pin "2") (pinfunction "D_2") (pintype "passive"))
    )
    (net (code "81") (name "Net-(Q3-G)") (class "Default")
      (node (ref "Q3") (pin "1") (pinfunction "G_1") (pintype "passive"))
      (node (ref "Q4") (pin "3") (pinfunction "C_3") (pintype "passive"))
      (node (ref "R10") (pin "2") (pinfunction "2_2") (pintype "passive"))
    )
    (net (code "82") (name "Net-(Q4-B)") (class "Default")
      (node (ref "Q4") (pin "1") (pinfunction "B_1") (pintype "passive"))
      (node (ref "R12") (pin "2") (pinfunction "2_2") (pintype "passive"))
    )
    (net (code "83") (name "Net-(Q5-B)") (class "Default")
      (node (ref "Q5") (pin "1") (pinfunction "B_1") (pintype "passive"))
      (node (ref "R14") (pin "1") (pinfunction "1_1") (pintype "passive"))
    )
    (net (code "84") (name "Net-(Q5-C)") (class "Default")
      (node (ref "LS1") (pin "2") (pinfunction "2_2") (pintype "passive"))
      (node (ref "Q5") (pin "3") (pinfunction "C_3") (pintype "passive"))
    )
    (net (code "85") (name "Net-(Q6-G)") (class "Default")
      (node (ref "Q6") (pin "1") (pinfunction "G_1") (pintype "passive"))
      (node (ref "Q7") (pin "3") (pinfunction "C_3") (pintype "passive"))
      (node (ref "R13") (pin "2") (pinfunction "2_2") (pintype "passive"))
    )
    (net (code "86") (name "Net-(Q7-B)") (class "Default")
      (node (ref "Q7") (pin "1") (pinfunction "B_1") (pintype "passive"))
      (node (ref "R16") (pin "2") (pinfunction "2_2") (pintype "passive"))
    )
    (net (code "87") (name "Net-(Q8-G)") (class "Default")
      (node (ref "Q8") (pin "1") (pinfunction "G_1") (pintype "passive"))
      (node (ref "Q9") (pin "3") (pinfunction "C_3") (pintype "passive"))
      (node (ref "R17") (pin "2") (pinfunction "2_2") (pintype "passive"))
    )
    (net (code "88") (name "Net-(Q9-B)") (class "Default")
      (node (ref "Q9") (pin "1") (pinfunction "B_1") (pintype "passive"))
      (node (ref "R22") (pin "2") (pinfunction "2_2") (pintype "passive"))
    )
    (net (code "89") (name "Net-(U2-VCC)") (class "Default")
      (node (ref "L2") (pin "1") (pinfunction "1_1") (pintype "passive"))
      (node (ref "U2") (pin "6") (pinfunction "VCC_6") (pintype "passive"))
    )
    (net (code "90") (name "Net-(U2-VIN1)") (class "Default")
      (node (ref "C1") (pin "2") (pinfunction "2_2") (pintype "passive"))
      (node (ref "U2") (pin "1") (pinfunction "VIN1_1") (pintype "passive"))
    )
    (net (code "91") (name "Net-(U2-VOUT1)") (class "Default")
      (node (ref "C2") (pin "2") (pinfunction "2_2") (pintype "passive"))
      (node (ref "U2") (pin "2") (pinfunction "VOUT1_2") (pintype "passive"))
    )
    (net (code "92") (name "Net-(U3-FB)") (class "Default")
      (node (ref "C8") (pin "1") (pinfunction "1_1") (pintype "passive"))
      (node (ref "L1") (pin "2") (pinfunction "2_2") (pintype "passive"))
      (node (ref "L3") (pin "1") (pinfunction "1_1") (pintype "passive"))
      (node (ref "U3") (pin "4") (pinfunction "FB_4") (pintype "input"))
    )
    (net (code "93") (name "Net-(U5-CH_PD)") (class "Default")
      (node (ref "R24") (pin "1") (pinfunction "1_1") (pintype "passive"))
      (node (ref "U5") (pin "3") (pinfunction "CH_PD_3") (pintype "passive"))
    )
    (net (code "94") (name "Net-(U5-GPIO15)") (class "Default")
      (node (ref "R28") (pin "1") (pinfunction "1_1") (pintype "passive"))
      (node (ref "U5") (pin "10") (pinfunction "GPIO15_10") (pintype "passive"))
    )
    (net (code "95") (name "Net-(U6A-INA+)") (class "Default")
      (node (ref "C16") (pin "2") (pinfunction "2_2") (pintype "passive"))
      (node (ref "R27") (pin "1") (pinfunction "1_1") (pintype "passive"))
      (node (ref "U6") (pin "3") (pinfunction "INA+_3") (pintype "input"))
    )
    (net (code "96") (name "Net-(U6A-INA-)") (class "Default")
      (node (ref "R26") (pin "2") (pinfunction "2_2") (pintype "passive"))
      (node (ref "U6") (pin "1") (pinfunction "OUTA_1") (pintype "output"))
      (node (ref "U6") (pin "2") (pinfunction "INA-_2") (pintype "input"))
    )
    (net (code "97") (name "Net-(U6B-INB+)") (class "Default")
      (node (ref "C25") (pin "2") (pinfunction "2_2") (pintype "passive"))
      (node (ref "R36") (pin "1") (pinfunction "1_1") (pintype "passive"))
      (node (ref "U6") (pin "5") (pinfunction "INB+_5") (pintype "input"))
    )
    (net (code "98") (name "Net-(U6B-INB-)") (class "Default")
      (node (ref "R32") (pin "2") (pinfunction "2_2") (pintype "passive"))
      (node (ref "U6") (pin "6") (pinfunction "INB-_6") (pintype "input"))
      (node (ref "U6") (pin "7") (pinfunction "OUTB_7") (pintype "output"))
    )
    (net (code "99") (name "Net-(U8-BYP)") (class "Default")
      (node (ref "C20") (pin "2") (pinfunction "2_2") (pintype "passive"))
      (node (ref "U8") (pin "2") (pinfunction "BYP_2") (pintype "passive"))
    )
    (net (code "100") (name "Net-(U8-SA0)") (class "Default")
      (node (ref "R37") (pin "2") (pinfunction "2_2") (pintype "passive"))
      (node (ref "U8") (pin "7") (pinfunction "SA0_7") (pintype "passive"))
    )
    (net (code "101") (name "Net-(U9A-INA+)") (class "Default")
      (node (ref "C22") (pin "2") (pinfunction "2_2") (pintype "passive"))
      (node (ref "R33") (pin "1") (pinfunction "1_1") (pintype "passive"))
      (node (ref "U9") (pin "3") (pinfunction "INA+_3") (pintype "input"))
    )
    (net (code "102") (name "Net-(U9A-INA-)") (class "Default")
      (node (ref "R31") (pin "2") (pinfunction "2_2") (pintype "passive"))
      (node (ref "U9") (pin "1") (pinfunction "OUTA_1") (pintype "output"))
      (node (ref "U9") (pin "2") (pinfunction "INA-_2") (pintype "input"))
    )
    (net (code "103") (name "Net-(U9B-INB+)") (class "Default")
      (node (ref "C30") (pin "2") (pinfunction "2_2") (pintype "passive"))
      (node (ref "R41") (pin "1") (pinfunction "1_1") (pintype "passive"))
      (node (ref "U9") (pin "5") (pinfunction "INB+_5") (pintype "input"))
    )
    (net (code "104") (name "Net-(U9B-INB-)") (class "Default")
      (node (ref "R40") (pin "2") (pinfunction "2_2") (pintype "passive"))
      (node (ref "U9") (pin "6") (pinfunction "INB-_6") (pintype "input"))
      (node (ref "U9") (pin "7") (pinfunction "OUTB_7") (pintype "output"))
    )
    (net (code "105") (name "Net-(U10A-BOOT0)") (class "Default")
      (node (ref "R54") (pin "2") (pinfunction "2_2") (pintype "passive"))
      (node (ref "U10") (pin "60") (pinfunction "BOOT0_60") (pintype "input"))
    )
    (net (code "106") (name "Net-(U10A-NRST)") (class "Default")
      (node (ref "C39") (pin "2") (pinfunction "2_2") (pintype "passive"))
      (node (ref "R57") (pin "2") (pinfunction "2_2") (pintype "passive"))
      (node (ref "S2") (pin "2") (pinfunction "2_2") (pintype "passive"))
      (node (ref "U10") (pin "7") (pinfunction "NRST_7") (pintype "bidirectional"))
    )
    (net (code "107") (name "Net-(U10A-PD0-OSC_IN)") (class "Default")
      (node (ref "C32") (pin "1") (pinfunction "1_1") (pintype "passive"))
      (node (ref "U10") (pin "5") (pinfunction "PD0-OSC_IN_5") (pintype "bidirectional"))
      (node (ref "Y1") (pin "2") (pinfunction "OSC2_2") (pintype "passive"))
    )
    (net (code "108") (name "Net-(U10A-PD1)") (class "Default")
      (node (ref "C33") (pin "1") (pinfunction "1_1") (pintype "passive"))
      (node (ref "U10") (pin "6") (pinfunction "PD1_6") (pintype "bidirectional"))
      (node (ref "Y1") (pin "1") (pinfunction "OSC1_1") (pintype "passive"))
    )
    (net (code "109") (name "Net-(U11A-INA+)") (class "Default")
      (node (ref "R45") (pin "2") (pinfunction "2_2") (pintype "passive"))
      (node (ref "U11") (pin "3") (pinfunction "INA+_3") (pintype "input"))
    )
    (net (code "110") (name "Net-(U11A-INA-)") (class "Default")
      (node (ref "R42") (pin "1") (pinfunction "1_1") (pintype "passive"))
      (node (ref "R44") (pin "2") (pinfunction "2_2") (pintype "passive"))
      (node (ref "U11") (pin "2") (pinfunction "INA-_2") (pintype "input"))
    )
    (net (code "111") (name "Net-(U11B-INB+)") (class "Default")
      (node (ref "R53") (pin "2") (pinfunction "2_2") (pintype "passive"))
      (node (ref "U11") (pin "5") (pinfunction "INB+_5") (pintype "input"))
    )
    (net (code "112") (name "Net-(U11B-INB-)") (class "Default")
      (node (ref "R51") (pin "1") (pinfunction "1_1") (pintype "passive"))
      (node (ref "R52") (pin "2") (pinfunction "2_2") (pintype "passive"))
      (node (ref "U11") (pin "6") (pinfunction "INB-_6") (pintype "input"))
    )
    (net (code "113") (name "Net-(U12A-INA+)") (class "Default")
      (node (ref "C35") (pin "2") (pinfunction "2_2") (pintype "passive"))
      (node (ref "R50") (pin "1") (pinfunction "1_1") (pintype "passive"))
      (node (ref "U12") (pin "3") (pinfunction "INA+_3") (pintype "input"))
    )
    (net (code "114") (name "Net-(U12A-INA-)") (class "Default")
      (node (ref "R49") (pin "2") (pinfunction "2_2") (pintype "passive"))
      (node (ref "U12") (pin "1") (pinfunction "OUTA_1") (pintype "output"))
      (node (ref "U12") (pin "2") (pinfunction "INA-_2") (pintype "input"))
    )
    (net (code "115") (name "Net-(U12B-INB+)") (class "Default")
      (node (ref "C41") (pin "2") (pinfunction "2_2") (pintype "passive"))
      (node (ref "R59") (pin "1") (pinfunction "1_1") (pintype "passive"))
      (node (ref "U12") (pin "5") (pinfunction "INB+_5") (pintype "input"))
    )
    (net (code "116") (name "Net-(U12B-INB-)") (class "Default")
      (node (ref "R58") (pin "2") (pinfunction "2_2") (pintype "passive"))
      (node (ref "U12") (pin "6") (pinfunction "INB-_6") (pintype "input"))
      (node (ref "U12") (pin "7") (pinfunction "OUTB_7") (pintype "output"))
    )
    (net (code "117") (name "Net-(U13-A)") (class "Default")
      (node (ref "R61") (pin "8") (pinfunction "8_8") (pintype "passive"))
      (node (ref "U13") (pin "1") (pinfunction "A_1") (pintype "passive"))
    )
    (net (code "118") (name "Net-(U13-C)") (class "Default")
      (node (ref "R60") (pin "1") (pinfunction "1_1") (pintype "passive"))
      (node (ref "U13") (pin "4") (pinfunction "C_4") (pintype "passive"))
    )
    (net (code "119") (name "Net-(U14-A)") (class "Default")
      (node (ref "R61") (pin "7") (pinfunction "7_7") (pintype "passive"))
      (node (ref "U14") (pin "1") (pinfunction "A_1") (pintype "passive"))
    )
    (net (code "120") (name "Net-(U14-C)") (class "Default")
      (node (ref "R60") (pin "2") (pinfunction "2_2") (pintype "passive"))
      (node (ref "U14") (pin "4") (pinfunction "C_4") (pintype "passive"))
    )
    (net (code "121") (name "Net-(U15-A)") (class "Default")
      (node (ref "R61") (pin "6") (pinfunction "6_6") (pintype "passive"))
      (node (ref "U15") (pin "1") (pinfunction "A_1") (pintype "passive"))
    )
    (net (code "122") (name "Net-(U15-C)") (class "Default")
      (node (ref "R60") (pin "3") (pinfunction "3_3") (pintype "passive"))
      (node (ref "U15") (pin "4") (pinfunction "C_4") (pintype "passive"))
    )
    (net (code "123") (name "Net-(U16-C)") (class "Default")
      (node (ref "R61") (pin "5") (pinfunction "5_5") (pintype "passive"))
      (node (ref "U16") (pin "4") (pinfunction "C_4") (pintype "passive"))
    )
    (net (code "124") (name "Net-(U16-K)") (class "Default")
      (node (ref "R60") (pin "4") (pinfunction "4_4") (pintype "passive"))
      (node (ref "U16") (pin "2") (pinfunction "K_2") (pintype "passive"))
    )
    (net (code "125") (name "Net-(U17-ABD)") (class "Default")
      (node (ref "R8") (pin "2") (pinfunction "2_2") (pintype "passive"))
      (node (ref "U17") (pin "2") (pinfunction "ABD_2") (pintype "passive"))
    )
    (net (code "126") (name "Net-(U17-IN+)") (class "Default")
      (node (ref "R9") (pin "2") (pinfunction "2_2") (pintype "passive"))
      (node (ref "U17") (pin "3") (pinfunction "IN+_3") (pintype "passive"))
    )
    (net (code "127") (name "Net-(U17-IN-)") (class "Default")
      (node (ref "R46") (pin "2") (pinfunction "2_2") (pintype "passive"))
      (node (ref "U17") (pin "4") (pinfunction "IN-_4") (pintype "passive"))
    )
    (net (code "128") (name "Net-(U17-SD)") (class "Default")
      (node (ref "R2") (pin "2") (pinfunction "2_2") (pintype "passive"))
      (node (ref "U17") (pin "1") (pinfunction "SD_1") (pintype "passive"))
    )
    (net (code "129") (name "Net-(U17-VO+)") (class "Default")
      (node (ref "P3") (pin "2") (pinfunction "2_2") (pintype "passive"))
      (node (ref "U17") (pin "6") (pinfunction "VO+_6") (pintype "passive"))
    )
    (net (code "130") (name "Net-(U17-VO-)") (class "Default")
      (node (ref "P3") (pin "1") (pinfunction "1_1") (pintype "passive"))
      (node (ref "U17") (pin "7") (pinfunction "VO-_7") (pintype "passive"))
    )
    (net (code "131") (name "PGND") (class "Default")
      (node (ref "C15") (pin "1") (pinfunction "1_1") (pintype "passive"))
      (node (ref "C16") (pin "1") (pinfunction "1_1") (pintype "passive"))
      (node (ref "C17") (pin "1") (pinfunction "1_1") (pintype "passive"))
      (node (ref "C21") (pin "1") (pinfunction "1_1") (pintype "passive"))
      (node (ref "C22") (pin "1") (pinfunction "1_1") (pintype "passive"))
      (node (ref "C23") (pin "1") (pinfunction "1_1") (pintype "passive"))
      (node (ref "C24") (pin "1") (pinfunction "1_1") (pintype "passive"))
      (node (ref "C25") (pin "1") (pinfunction "1_1") (pintype "passive"))
      (node (ref "C26") (pin "1") (pinfunction "1_1") (pintype "passive"))
      (node (ref "C29") (pin "1") (pinfunction "1_1") (pintype "passive"))
      (node (ref "C3") (pin "1") (pinfunction "1_1") (pintype "passive"))
      (node (ref "C30") (pin "1") (pinfunction "1_1") (pintype "passive"))
      (node (ref "C31") (pin "1") (pinfunction "1_1") (pintype "passive"))
      (node (ref "C34") (pin "1") (pinfunction "1_1") (pintype "passive"))
      (node (ref "C35") (pin "1") (pinfunction "1_1") (pintype "passive"))
      (node (ref "C36") (pin "1") (pinfunction "1_1") (pintype "passive"))
      (node (ref "C40") (pin "1") (pinfunction "1_1") (pintype "passive"))
      (node (ref "C41") (pin "1") (pinfunction "1_1") (pintype "passive"))
      (node (ref "C42") (pin "1") (pinfunction "1_1") (pintype "passive"))
      (node (ref "C45") (pin "2") (pinfunction "2_2") (pintype "passive"))
      (node (ref "C46") (pin "2") (pinfunction "2_2") (pintype "passive"))
      (node (ref "C47") (pin "2") (pinfunction "2_2") (pintype "passive"))
      (node (ref "C49") (pin "2") (pinfunction "2_2") (pintype "passive"))
      (node (ref "C50") (pin "2") (pinfunction "2_2") (pintype "passive"))
      (node (ref "C6") (pin "2") (pinfunction "2_2") (pintype "passive"))
      (node (ref "C7") (pin "2") (pinfunction "2_2") (pintype "passive"))
      (node (ref "C8") (pin "2") (pinfunction "2_2") (pintype "passive"))
      (node (ref "D10") (pin "1") (pinfunction "A_1") (pintype "passive"))
      (node (ref "D11") (pin "1") (pinfunction "A_1") (pintype "passive"))
      (node (ref "D13") (pin "1") (pinfunction "A_1") (pintype "passive"))
      (node (ref "D15") (pin "1") (pinfunction "A_1") (pintype "passive"))
      (node (ref "D17") (pin "1") (pinfunction "A_1") (pintype "passive"))
      (node (ref "D2") (pin "2") (pinfunction "K_2") (pintype "passive"))
      (node (ref "D4") (pin "1") (pinfunction "A_1") (pintype "passive"))
      (node (ref "D7") (pin "1") (pinfunction "A_1") (pintype "passive"))
      (node (ref "P1") (pin "2") (pinfunction "2_2") (pintype "passive"))
      (node (ref "P10") (pin "3") (pinfunction "3_3") (pintype "passive"))
      (node (ref "P11") (pin "3") (pinfunction "3_3") (pintype "passive"))
      (node (ref "P14") (pin "2") (pinfunction "2_2") (pintype "passive"))
      (node (ref "P15") (pin "2") (pinfunction "2_2") (pintype "passive"))
      (node (ref "P5") (pin "3") (pinfunction "3_3") (pintype "passive"))
      (node (ref "P7") (pin "7") (pinfunction "7_7") (pintype "passive"))
      (node (ref "P8") (pin "11") (pinfunction "GND_11") (pintype "passive"))
      (node (ref "P8") (pin "2") (pinfunction "GND_2") (pintype "passive"))
      (node (ref "Q1") (pin "3") (pinfunction "S_3") (pintype "passive"))
      (node (ref "Q3") (pin "3") (pinfunction "S_3") (pintype "passive"))
      (node (ref "Q5") (pin "2") (pinfunction "E_2") (pintype "passive"))
      (node (ref "Q6") (pin "3") (pinfunction "S_3") (pintype "passive"))
      (node (ref "Q8") (pin "3") (pinfunction "S_3") (pintype "passive"))
      (node (ref "R3") (pin "1") (pinfunction "1_1") (pintype "passive"))
      (node (ref "R45") (pin "1") (pinfunction "1_1") (pintype "passive"))
      (node (ref "R5") (pin "2") (pinfunction "2_2") (pintype "passive"))
      (node (ref "R53") (pin "1") (pinfunction "1_1") (pintype "passive"))
      (node (ref "R8") (pin "1") (pinfunction "1_1") (pintype "passive"))
      (node (ref "R9") (pin "1") (pinfunction "1_1") (pintype "passive"))
      (node (ref "U1") (pin "5") (pinfunction "H_5") (pintype "passive"))
      (node (ref "U11") (pin "4") (pinfunction "GND_4") (pintype "power_in"))
      (node (ref "U12") (pin "4") (pinfunction "GND_4") (pintype "power_in"))
      (node (ref "U13") (pin "3") (pinfunction "E_3") (pintype "passive"))
      (node (ref "U14") (pin "3") (pinfunction "E_3") (pintype "passive"))
      (node (ref "U15") (pin "3") (pinfunction "E_3") (pintype "passive"))
      (node (ref "U17") (pin "8") (pinfunction "GND_8") (pintype "passive"))
      (node (ref "U2") (pin "3") (pinfunction "GND_3") (pintype "passive"))
      (node (ref "U3") (pin "3") (pinfunction "GND_3") (pintype "power_in"))
      (node (ref "U3") (pin "5") (pinfunction "~{ON}/OFF_5") (pintype "input"))
      (node (ref "U6") (pin "4") (pinfunction "GND_4") (pintype "power_in"))
      (node (ref "U9") (pin "4") (pinfunction "GND_4") (pintype "power_in"))
    )
    (net (code "132") (name "SGND") (class "Default")
      (node (ref "C10") (pin "2") (pinfunction "2_2") (pintype "passive"))
      (node (ref "C11") (pin "2") (pinfunction "2_2") (pintype "passive"))
      (node (ref "C13") (pin "2") (pinfunction "2_2") (pintype "passive"))
      (node (ref "C14") (pin "2") (pinfunction "2_2") (pintype "passive"))
      (node (ref "C20") (pin "1") (pinfunction "1_1") (pintype "passive"))
      (node (ref "C32") (pin "2") (pinfunction "2_2") (pintype "passive"))
      (node (ref "C33") (pin "2") (pinfunction "2_2") (pintype "passive"))
      (node (ref "C37") (pin "2") (pinfunction "2_2") (pintype "passive"))
      (node (ref "C38") (pin "2") (pinfunction "2_2") (pintype "passive"))
      (node (ref "C39") (pin "1") (pinfunction "1_1") (pintype "passive"))
      (node (ref "C43") (pin "2") (pinfunction "2_2") (pintype "passive"))
      (node (ref "C44") (pin "2") (pinfunction "2_2") (pintype "passive"))
      (node (ref "P12") (pin "4") (pinfunction "4_4") (pintype "passive"))
      (node (ref "P13") (pin "4") (pinfunction "4_4") (pintype "passive"))
      (node (ref "Q2") (pin "2") (pinfunction "E_2") (pintype "passive"))
      (node (ref "Q4") (pin "2") (pinfunction "E_2") (pintype "passive"))
      (node (ref "Q7") (pin "2") (pinfunction "E_2") (pintype "passive"))
      (node (ref "Q9") (pin "2") (pinfunction "E_2") (pintype "passive"))
      (node (ref "R28") (pin "2") (pinfunction "2_2") (pintype "passive"))
      (node (ref "R3") (pin "2") (pinfunction "2_2") (pintype "passive"))
      (node (ref "R37") (pin "1") (pinfunction "1_1") (pintype "passive"))
      (node (ref "R43") (pin "1") (pinfunction "1_1") (pintype "passive"))
      (node (ref "R48") (pin "1") (pinfunction "A0_1") (pintype "passive"))
      (node (ref "R48") (pin "2") (pinfunction "A1_2") (pintype "passive"))
      (node (ref "R48") (pin "3") (pinfunction "A2_3") (pintype "passive"))
      (node (ref "R48") (pin "4") (pinfunction "GND_4") (pintype "passive"))
      (node (ref "R48") (pin "7") (pinfunction "WP_7") (pintype "passive"))
      (node (ref "R54") (pin "1") (pinfunction "1_1") (pintype "passive"))
      (node (ref "S1") (pin "10") (pinfunction "B7_10") (pintype "passive"))
      (node (ref "S1") (pin "11") (pinfunction "B6_11") (pintype "passive"))
      (node (ref "S1") (pin "12") (pinfunction "B5_12") (pintype "passive"))
      (node (ref "S1") (pin "13") (pinfunction "B4_13") (pintype "passive"))
      (node (ref "S1") (pin "14") (pinfunction "B3_14") (pintype "passive"))
      (node (ref "S1") (pin "15") (pinfunction "B2_15") (pintype "passive"))
      (node (ref "S1") (pin "16") (pinfunction "B1_16") (pintype "passive"))
      (node (ref "S1") (pin "9") (pinfunction "B8_9") (pintype "passive"))
      (node (ref "S2") (pin "1") (pinfunction "1_1") (pintype "passive"))
      (node (ref "U10") (pin "12") (pinfunction "VSSA_12") (pintype "power_in"))
      (node (ref "U10") (pin "18") (pinfunction "VSS_4_18") (pintype "power_in"))
      (node (ref "U10") (pin "31") (pinfunction "VSS_1_31") (pintype "power_in"))
      (node (ref "U10") (pin "47") (pinfunction "VSS_2_47") (pintype "power_in"))
      (node (ref "U10") (pin "63") (pinfunction "VSS_3_63") (pintype "power_in"))
      (node (ref "U13") (pin "2") (pinfunction "K_2") (pintype "passive"))
      (node (ref "U14") (pin "2") (pinfunction "K_2") (pintype "passive"))
      (node (ref "U15") (pin "2") (pinfunction "K_2") (pintype "passive"))
      (node (ref "U16") (pin "3") (pinfunction "E_3") (pintype "passive"))
      (node (ref "U4") (pin "1") (pinfunction "Ground_1") (pintype "passive"))
      (node (ref "U5") (pin "9") (pinfunction "GND_9") (pintype "passive"))
      (node (ref "U7") (pin "1") (pinfunction "GND_1") (pintype "passive"))
      (node (ref "U8") (pin "10") (pinfunction "GND_10") (pintype "passive"))
      (node (ref "U8") (pin "12") (pinfunction "GND_12") (pintype "passive"))
      (node (ref "U8") (pin "5") (pinfunction "GND_5") (pintype "passive"))
    )
    (net (code "133") (name "unconnected-(P7-Pad6)") (class "Default")
      (node (ref "P7") (pin "6") (pinfunction "6_6") (pintype "passive+no_connect"))
    )
    (net (code "134") (name "unconnected-(P8-ANT-Pad1)") (class "Default")
      (node (ref "P8") (pin "1") (pinfunction "ANT_1") (pintype "passive+no_connect"))
    )
    (net (code "135") (name "unconnected-(P8-D3-Pad9)") (class "Default")
      (node (ref "P8") (pin "9") (pinfunction "D3_9") (pintype "passive+no_connect"))
    )
    (net (code "136") (name "unconnected-(P8-VT-Pad5)") (class "Default")
      (node (ref "P8") (pin "5") (pinfunction "VT_5") (pintype "passive+no_connect"))
    )
    (net (code "137") (name "unconnected-(U1-A-Pad3)") (class "Default")
      (node (ref "U1") (pin "3") (pinfunction "A_3") (pintype "passive+no_connect"))
    )
    (net (code "138") (name "unconnected-(U1-B-Pad4)") (class "Default")
      (node (ref "U1") (pin "4") (pinfunction "B_4") (pintype "passive+no_connect"))
    )
    (net (code "139") (name "unconnected-(U2-VIN2-Pad8)") (class "Default")
      (node (ref "U2") (pin "8") (pinfunction "VIN2_8") (pintype "passive+no_connect"))
    )
    (net (code "140") (name "unconnected-(U2-VOUT2-Pad7)") (class "Default")
      (node (ref "U2") (pin "7") (pinfunction "VOUT2_7") (pintype "passive+no_connect"))
    )
    (net (code "141") (name "unconnected-(U3-TAB-Pad6)") (class "Default")
      (node (ref "U3") (pin "6") (pinfunction "TAB_6") (pintype "power_in+no_connect"))
    )
    (net (code "142") (name "unconnected-(U5-ADC-Pad2)") (class "Default")
      (node (ref "U5") (pin "2") (pinfunction "ADC_2") (pintype "passive+no_connect"))
    )
    (net (code "143") (name "unconnected-(U5-GPIO0-Pad12)") (class "Default")
      (node (ref "U5") (pin "12") (pinfunction "GPIO0_12") (pintype "passive+no_connect"))
    )
    (net (code "144") (name "unconnected-(U5-GPIO2-Pad11)") (class "Default")
      (node (ref "U5") (pin "11") (pinfunction "GPIO2_11") (pintype "passive+no_connect"))
    )
    (net (code "145") (name "unconnected-(U5-GPIO4-Pad14)") (class "Default")
      (node (ref "U5") (pin "14") (pinfunction "GPIO4_14") (pintype "passive+no_connect"))
    )
    (net (code "146") (name "unconnected-(U5-GPIO5-Pad13)") (class "Default")
      (node (ref "U5") (pin "13") (pinfunction "GPIO5_13") (pintype "passive+no_connect"))
    )
    (net (code "147") (name "unconnected-(U5-GPIO12-Pad6)") (class "Default")
      (node (ref "U5") (pin "6") (pinfunction "GPIO12_6") (pintype "passive+no_connect"))
    )
    (net (code "148") (name "unconnected-(U5-GPIO13-Pad7)") (class "Default")
      (node (ref "U5") (pin "7") (pinfunction "GPIO13_7") (pintype "passive+no_connect"))
    )
    (net (code "149") (name "unconnected-(U5-GPIO14-Pad5)") (class "Default")
      (node (ref "U5") (pin "5") (pinfunction "GPIO14_5") (pintype "passive+no_connect"))
    )
    (net (code "150") (name "unconnected-(U5-GPIO16-Pad4)") (class "Default")
      (node (ref "U5") (pin "4") (pinfunction "GPIO16_4") (pintype "passive+no_connect"))
    )
    (net (code "151") (name "unconnected-(U8-INT1-Pad11)") (class "Default")
      (node (ref "U8") (pin "11") (pinfunction "INT1_11") (pintype "passive+no_connect"))
    )
    (net (code "152") (name "unconnected-(U8-INT2-Pad9)") (class "Default")
      (node (ref "U8") (pin "9") (pinfunction "INT2_9") (pintype "passive+no_connect"))
    )
    (net (code "153") (name "unconnected-(U8-NC-Pad3)") (class "Default")
      (node (ref "U8") (pin "3") (pinfunction "NC_3") (pintype "passive"))
    )
    (net (code "154") (name "unconnected-(U8-NC-Pad8)") (class "Default")
      (node (ref "U8") (pin "8") (pinfunction "NC_8") (pintype "passive"))
    )
    (net (code "155") (name "unconnected-(U8-NC-Pad13)") (class "Default")
      (node (ref "U8") (pin "13") (pinfunction "NC_13") (pintype "passive"))
    )
    (net (code "156") (name "unconnected-(U8-NC-Pad15)") (class "Default")
      (node (ref "U8") (pin "15") (pinfunction "NC_15") (pintype "passive"))
    )
    (net (code "157") (name "unconnected-(U8-NC-Pad16)") (class "Default")
      (node (ref "U8") (pin "16") (pinfunction "NC_16") (pintype "passive"))
    )
    (net (code "158") (name "unconnected-(U10A-PC13-TAMPER-RTC-Pad2)") (class "Default")
      (node (ref "U10") (pin "2") (pinfunction "PC13-TAMPER-RTC_2") (pintype "bidirectional+no_connect"))
    )
    (net (code "159") (name "unconnected-(U10A-PC14-OSC32_IN-Pad3)") (class "Default")
      (node (ref "U10") (pin "3") (pinfunction "PC14-OSC32_IN_3") (pintype "bidirectional+no_connect"))
    )
    (net (code "160") (name "unconnected-(U10A-PC15-OSC32_OUT-Pad4)") (class "Default")
      (node (ref "U10") (pin "4") (pinfunction "PC15-OSC32_OUT_4") (pintype "bidirectional+no_connect"))
    )
    (net (code "161") (name "unconnected-(U10B-VBAT-Pad1)") (class "Default")
      (node (ref "U10") (pin "1") (pinfunction "VBAT_1") (pintype "power_in+no_connect"))
    )
  )
)
